# qdr2_3.net
KiCad netlist of a schematic drawn in Altium Designer
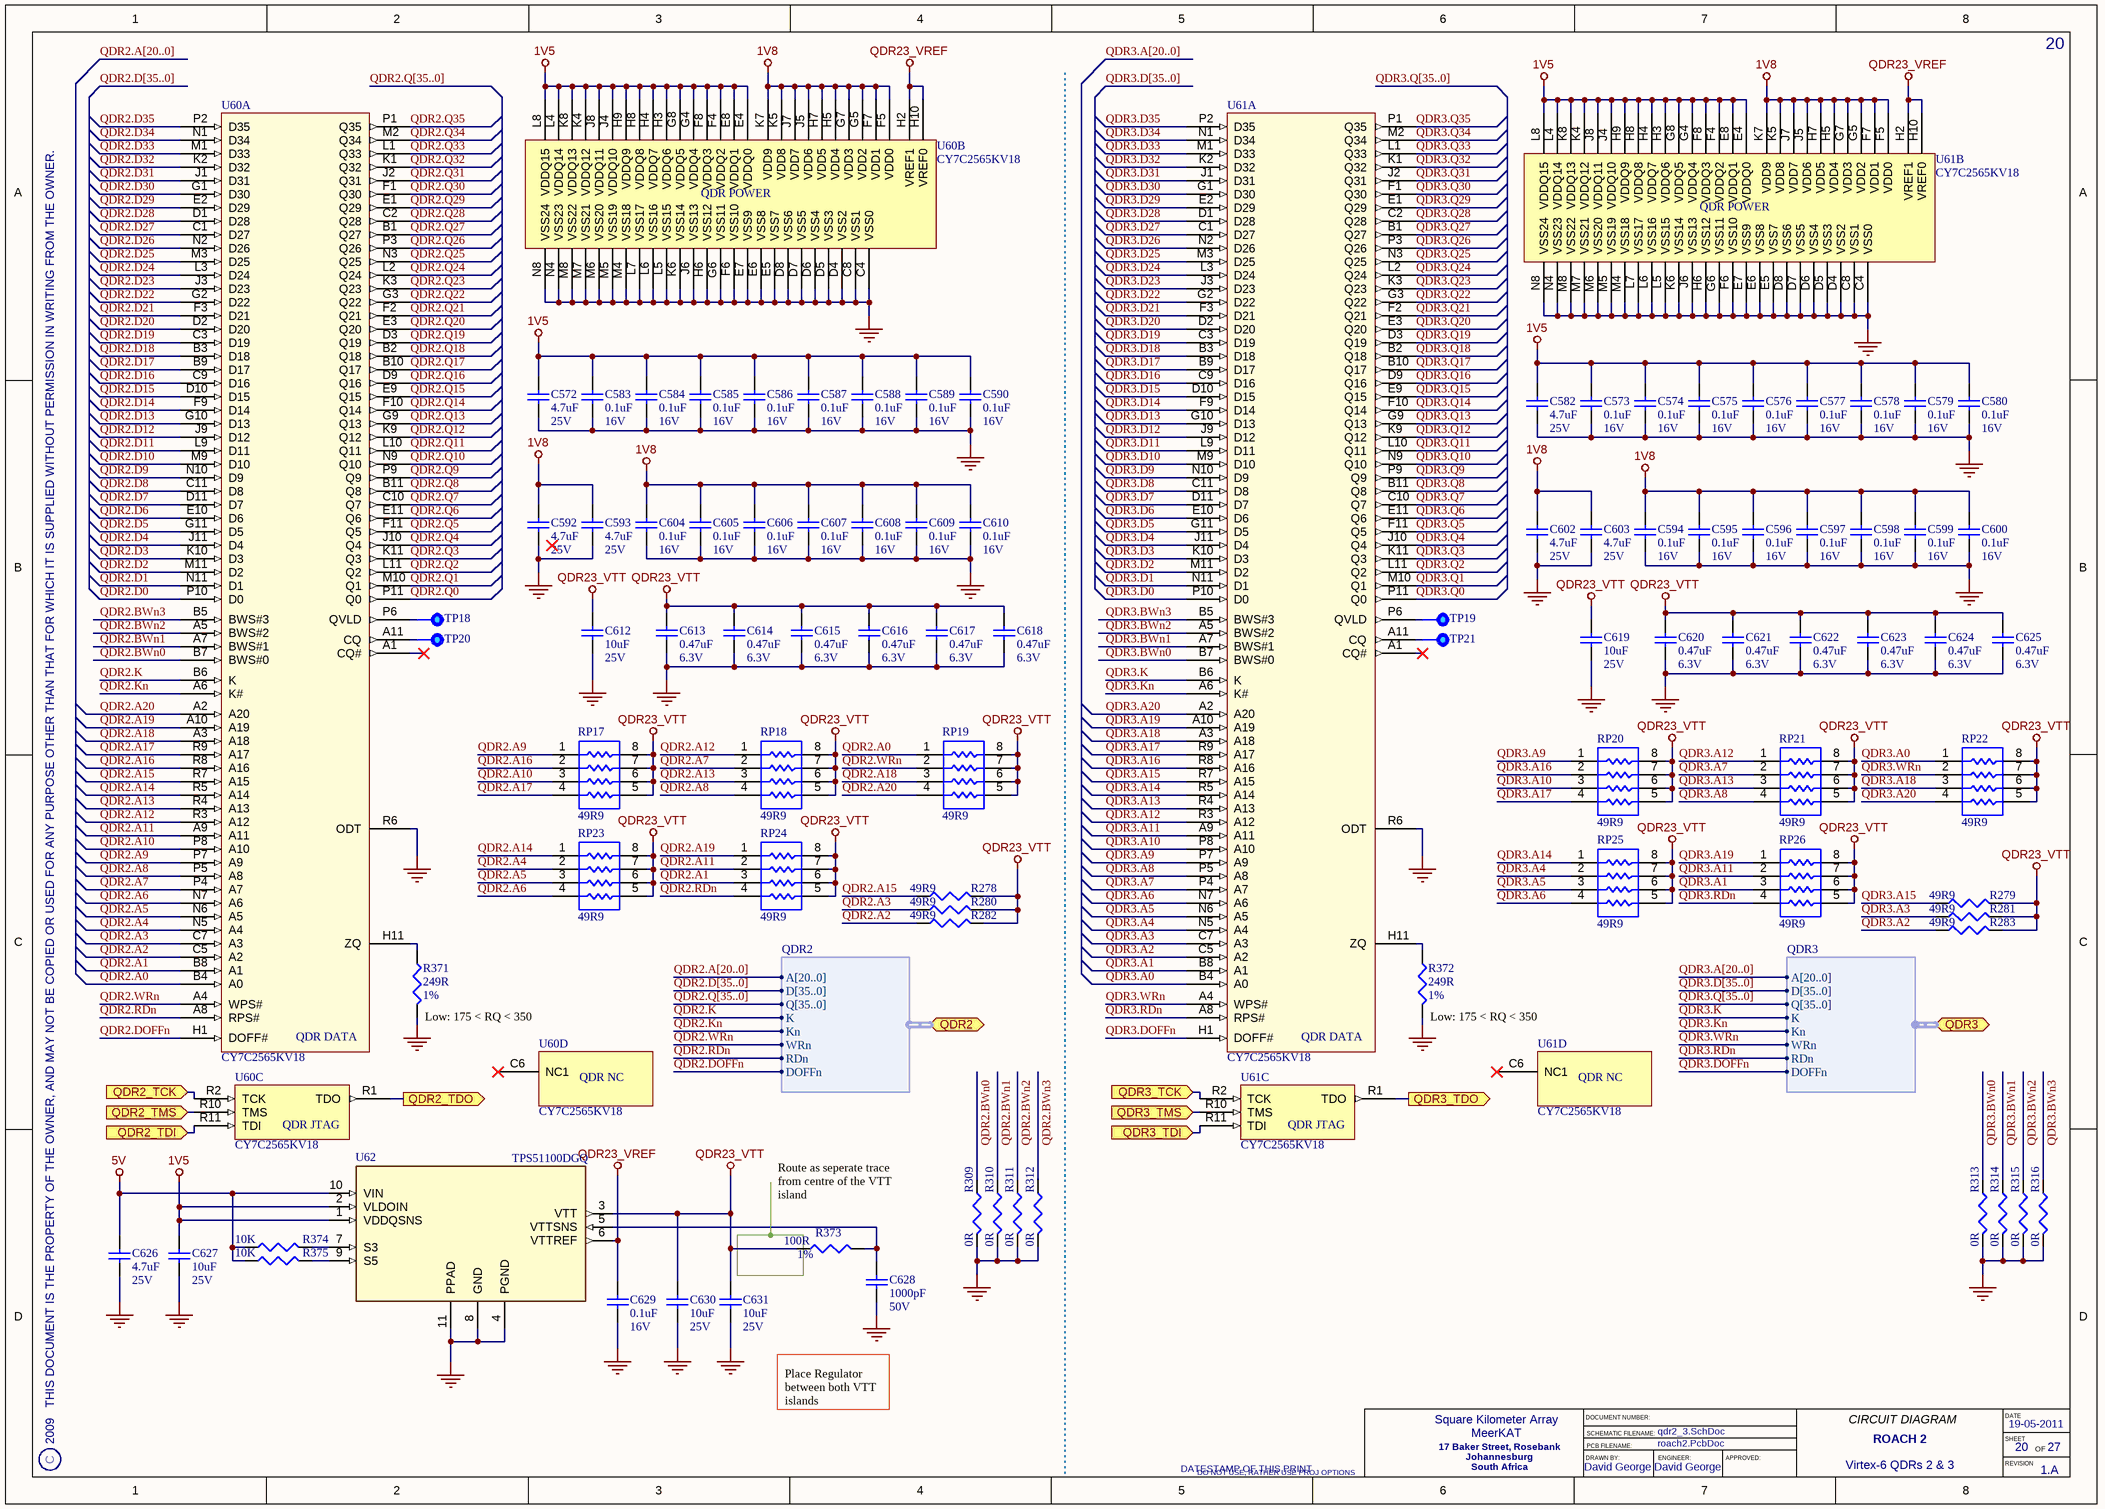
[diagram p0: qdr2_3.SchDoc]

(export (version "E")
  (design (tool "Eeschema 10.0.6"))
  (components
    (comp (ref "C572")
      (value "4.7uF")
      (footprint "CAPC2012X127L")
      (description "4.7uF, Ceramic Capacitor")
      (fields
        (field (name "RATING") "25V")
        (field (name "MANUFACTURER") "MURATA")
        (field (name "PARTNUM") "GRM21BR61E475KA12K")
      )
      (libsource (lib "altium_db") (part "CapStd"))
    )
    (comp (ref "C573")
      (value "0.1uF")
      (footprint "CAPC1005X60L")
      (description "0.1uF, Ceramic Capacitor")
      (fields
        (field (name "RATING") "16V")
        (field (name "MANUFACTURER") "VENKEL")
        (field (name "PARTNUM") "C0402X7R160-104KN")
      )
      (libsource (lib "altium_db") (part "CapStd"))
    )
    (comp (ref "C574")
      (value "0.1uF")
      (footprint "CAPC1005X60L")
      (description "0.1uF, Ceramic Capacitor")
      (fields
        (field (name "RATING") "16V")
        (field (name "MANUFACTURER") "VENKEL")
        (field (name "PARTNUM") "C0402X7R160-104KN")
      )
      (libsource (lib "altium_db") (part "CapStd"))
    )
    (comp (ref "C575")
      (value "0.1uF")
      (footprint "CAPC1005X60L")
      (description "0.1uF, Ceramic Capacitor")
      (fields
        (field (name "RATING") "16V")
        (field (name "MANUFACTURER") "VENKEL")
        (field (name "PARTNUM") "C0402X7R160-104KN")
      )
      (libsource (lib "altium_db") (part "CapStd"))
    )
    (comp (ref "C576")
      (value "0.1uF")
      (footprint "CAPC1005X60L")
      (description "0.1uF, Ceramic Capacitor")
      (fields
        (field (name "RATING") "16V")
        (field (name "MANUFACTURER") "VENKEL")
        (field (name "PARTNUM") "C0402X7R160-104KN")
      )
      (libsource (lib "altium_db") (part "CapStd"))
    )
    (comp (ref "C577")
      (value "0.1uF")
      (footprint "CAPC1005X60L")
      (description "0.1uF, Ceramic Capacitor")
      (fields
        (field (name "RATING") "16V")
        (field (name "MANUFACTURER") "VENKEL")
        (field (name "PARTNUM") "C0402X7R160-104KN")
      )
      (libsource (lib "altium_db") (part "CapStd"))
    )
    (comp (ref "C578")
      (value "0.1uF")
      (footprint "CAPC1005X60L")
      (description "0.1uF, Ceramic Capacitor")
      (fields
        (field (name "RATING") "16V")
        (field (name "MANUFACTURER") "VENKEL")
        (field (name "PARTNUM") "C0402X7R160-104KN")
      )
      (libsource (lib "altium_db") (part "CapStd"))
    )
    (comp (ref "C579")
      (value "0.1uF")
      (footprint "CAPC1005X60L")
      (description "0.1uF, Ceramic Capacitor")
      (fields
        (field (name "RATING") "16V")
        (field (name "MANUFACTURER") "VENKEL")
        (field (name "PARTNUM") "C0402X7R160-104KN")
      )
      (libsource (lib "altium_db") (part "CapStd"))
    )
    (comp (ref "C580")
      (value "0.1uF")
      (footprint "CAPC1005X60L")
      (description "0.1uF, Ceramic Capacitor")
      (fields
        (field (name "RATING") "16V")
        (field (name "MANUFACTURER") "VENKEL")
        (field (name "PARTNUM") "C0402X7R160-104KN")
      )
      (libsource (lib "altium_db") (part "CapStd"))
    )
    (comp (ref "C582")
      (value "4.7uF")
      (footprint "CAPC2012X127L")
      (description "4.7uF, Ceramic Capacitor")
      (fields
        (field (name "RATING") "25V")
        (field (name "MANUFACTURER") "MURATA")
        (field (name "PARTNUM") "GRM21BR61E475KA12K")
      )
      (libsource (lib "altium_db") (part "CapStd"))
    )
    (comp (ref "C583")
      (value "0.1uF")
      (footprint "CAPC1005X60L")
      (description "0.1uF, Ceramic Capacitor")
      (fields
        (field (name "RATING") "16V")
        (field (name "MANUFACTURER") "VENKEL")
        (field (name "PARTNUM") "C0402X7R160-104KN")
      )
      (libsource (lib "altium_db") (part "CapStd"))
    )
    (comp (ref "C584")
      (value "0.1uF")
      (footprint "CAPC1005X60L")
      (description "0.1uF, Ceramic Capacitor")
      (fields
        (field (name "RATING") "16V")
        (field (name "MANUFACTURER") "VENKEL")
        (field (name "PARTNUM") "C0402X7R160-104KN")
      )
      (libsource (lib "altium_db") (part "CapStd"))
    )
    (comp (ref "C585")
      (value "0.1uF")
      (footprint "CAPC1005X60L")
      (description "0.1uF, Ceramic Capacitor")
      (fields
        (field (name "RATING") "16V")
        (field (name "MANUFACTURER") "VENKEL")
        (field (name "PARTNUM") "C0402X7R160-104KN")
      )
      (libsource (lib "altium_db") (part "CapStd"))
    )
    (comp (ref "C586")
      (value "0.1uF")
      (footprint "CAPC1005X60L")
      (description "0.1uF, Ceramic Capacitor")
      (fields
        (field (name "RATING") "16V")
        (field (name "MANUFACTURER") "VENKEL")
        (field (name "PARTNUM") "C0402X7R160-104KN")
      )
      (libsource (lib "altium_db") (part "CapStd"))
    )
    (comp (ref "C587")
      (value "0.1uF")
      (footprint "CAPC1005X60L")
      (description "0.1uF, Ceramic Capacitor")
      (fields
        (field (name "RATING") "16V")
        (field (name "MANUFACTURER") "VENKEL")
        (field (name "PARTNUM") "C0402X7R160-104KN")
      )
      (libsource (lib "altium_db") (part "CapStd"))
    )
    (comp (ref "C588")
      (value "0.1uF")
      (footprint "CAPC1005X60L")
      (description "0.1uF, Ceramic Capacitor")
      (fields
        (field (name "RATING") "16V")
        (field (name "MANUFACTURER") "VENKEL")
        (field (name "PARTNUM") "C0402X7R160-104KN")
      )
      (libsource (lib "altium_db") (part "CapStd"))
    )
    (comp (ref "C589")
      (value "0.1uF")
      (footprint "CAPC1005X60L")
      (description "0.1uF, Ceramic Capacitor")
      (fields
        (field (name "RATING") "16V")
        (field (name "MANUFACTURER") "VENKEL")
        (field (name "PARTNUM") "C0402X7R160-104KN")
      )
      (libsource (lib "altium_db") (part "CapStd"))
    )
    (comp (ref "C590")
      (value "0.1uF")
      (footprint "CAPC1005X60L")
      (description "0.1uF, Ceramic Capacitor")
      (fields
        (field (name "RATING") "16V")
        (field (name "MANUFACTURER") "VENKEL")
        (field (name "PARTNUM") "C0402X7R160-104KN")
      )
      (libsource (lib "altium_db") (part "CapStd"))
    )
    (comp (ref "C592")
      (value "4.7uF")
      (footprint "CAPC2012X127L")
      (description "4.7uF, Ceramic Capacitor")
      (fields
        (field (name "RATING") "25V")
        (field (name "MANUFACTURER") "MURATA")
        (field (name "PARTNUM") "GRM21BR61E475KA12K")
      )
      (libsource (lib "altium_db") (part "CapStd"))
    )
    (comp (ref "C593")
      (value "4.7uF")
      (footprint "CAPC2012X127L")
      (description "4.7uF, Ceramic Capacitor")
      (fields
        (field (name "RATING") "25V")
        (field (name "MANUFACTURER") "MURATA")
        (field (name "PARTNUM") "GRM21BR61E475KA12K")
      )
      (libsource (lib "altium_db") (part "CapStd"))
    )
    (comp (ref "C594")
      (value "0.1uF")
      (footprint "CAPC1005X60L")
      (description "0.1uF, Ceramic Capacitor")
      (fields
        (field (name "RATING") "16V")
        (field (name "MANUFACTURER") "VENKEL")
        (field (name "PARTNUM") "C0402X7R160-104KN")
      )
      (libsource (lib "altium_db") (part "CapStd"))
    )
    (comp (ref "C595")
      (value "0.1uF")
      (footprint "CAPC1005X60L")
      (description "0.1uF, Ceramic Capacitor")
      (fields
        (field (name "RATING") "16V")
        (field (name "MANUFACTURER") "VENKEL")
        (field (name "PARTNUM") "C0402X7R160-104KN")
      )
      (libsource (lib "altium_db") (part "CapStd"))
    )
    (comp (ref "C596")
      (value "0.1uF")
      (footprint "CAPC1005X60L")
      (description "0.1uF, Ceramic Capacitor")
      (fields
        (field (name "RATING") "16V")
        (field (name "MANUFACTURER") "VENKEL")
        (field (name "PARTNUM") "C0402X7R160-104KN")
      )
      (libsource (lib "altium_db") (part "CapStd"))
    )
    (comp (ref "C597")
      (value "0.1uF")
      (footprint "CAPC1005X60L")
      (description "0.1uF, Ceramic Capacitor")
      (fields
        (field (name "RATING") "16V")
        (field (name "MANUFACTURER") "VENKEL")
        (field (name "PARTNUM") "C0402X7R160-104KN")
      )
      (libsource (lib "altium_db") (part "CapStd"))
    )
    (comp (ref "C598")
      (value "0.1uF")
      (footprint "CAPC1005X60L")
      (description "0.1uF, Ceramic Capacitor")
      (fields
        (field (name "RATING") "16V")
        (field (name "MANUFACTURER") "VENKEL")
        (field (name "PARTNUM") "C0402X7R160-104KN")
      )
      (libsource (lib "altium_db") (part "CapStd"))
    )
    (comp (ref "C599")
      (value "0.1uF")
      (footprint "CAPC1005X60L")
      (description "0.1uF, Ceramic Capacitor")
      (fields
        (field (name "RATING") "16V")
        (field (name "MANUFACTURER") "VENKEL")
        (field (name "PARTNUM") "C0402X7R160-104KN")
      )
      (libsource (lib "altium_db") (part "CapStd"))
    )
    (comp (ref "C600")
      (value "0.1uF")
      (footprint "CAPC1005X60L")
      (description "0.1uF, Ceramic Capacitor")
      (fields
        (field (name "RATING") "16V")
        (field (name "MANUFACTURER") "VENKEL")
        (field (name "PARTNUM") "C0402X7R160-104KN")
      )
      (libsource (lib "altium_db") (part "CapStd"))
    )
    (comp (ref "C602")
      (value "4.7uF")
      (footprint "CAPC2012X127L")
      (description "4.7uF, Ceramic Capacitor")
      (fields
        (field (name "RATING") "25V")
        (field (name "MANUFACTURER") "MURATA")
        (field (name "PARTNUM") "GRM21BR61E475KA12K")
      )
      (libsource (lib "altium_db") (part "CapStd"))
    )
    (comp (ref "C603")
      (value "4.7uF")
      (footprint "CAPC2012X127L")
      (description "4.7uF, Ceramic Capacitor")
      (fields
        (field (name "RATING") "25V")
        (field (name "MANUFACTURER") "MURATA")
        (field (name "PARTNUM") "GRM21BR61E475KA12K")
      )
      (libsource (lib "altium_db") (part "CapStd"))
    )
    (comp (ref "C604")
      (value "0.1uF")
      (footprint "CAPC1005X60L")
      (description "0.1uF, Ceramic Capacitor")
      (fields
        (field (name "RATING") "16V")
        (field (name "MANUFACTURER") "VENKEL")
        (field (name "PARTNUM") "C0402X7R160-104KN")
      )
      (libsource (lib "altium_db") (part "CapStd"))
    )
    (comp (ref "C605")
      (value "0.1uF")
      (footprint "CAPC1005X60L")
      (description "0.1uF, Ceramic Capacitor")
      (fields
        (field (name "RATING") "16V")
        (field (name "MANUFACTURER") "VENKEL")
        (field (name "PARTNUM") "C0402X7R160-104KN")
      )
      (libsource (lib "altium_db") (part "CapStd"))
    )
    (comp (ref "C606")
      (value "0.1uF")
      (footprint "CAPC1005X60L")
      (description "0.1uF, Ceramic Capacitor")
      (fields
        (field (name "RATING") "16V")
        (field (name "MANUFACTURER") "VENKEL")
        (field (name "PARTNUM") "C0402X7R160-104KN")
      )
      (libsource (lib "altium_db") (part "CapStd"))
    )
    (comp (ref "C607")
      (value "0.1uF")
      (footprint "CAPC1005X60L")
      (description "0.1uF, Ceramic Capacitor")
      (fields
        (field (name "RATING") "16V")
        (field (name "MANUFACTURER") "VENKEL")
        (field (name "PARTNUM") "C0402X7R160-104KN")
      )
      (libsource (lib "altium_db") (part "CapStd"))
    )
    (comp (ref "C608")
      (value "0.1uF")
      (footprint "CAPC1005X60L")
      (description "0.1uF, Ceramic Capacitor")
      (fields
        (field (name "RATING") "16V")
        (field (name "MANUFACTURER") "VENKEL")
        (field (name "PARTNUM") "C0402X7R160-104KN")
      )
      (libsource (lib "altium_db") (part "CapStd"))
    )
    (comp (ref "C609")
      (value "0.1uF")
      (footprint "CAPC1005X60L")
      (description "0.1uF, Ceramic Capacitor")
      (fields
        (field (name "RATING") "16V")
        (field (name "MANUFACTURER") "VENKEL")
        (field (name "PARTNUM") "C0402X7R160-104KN")
      )
      (libsource (lib "altium_db") (part "CapStd"))
    )
    (comp (ref "C610")
      (value "0.1uF")
      (footprint "CAPC1005X60L")
      (description "0.1uF, Ceramic Capacitor")
      (fields
        (field (name "RATING") "16V")
        (field (name "MANUFACTURER") "VENKEL")
        (field (name "PARTNUM") "C0402X7R160-104KN")
      )
      (libsource (lib "altium_db") (part "CapStd"))
    )
    (comp (ref "C612")
      (value "10uF")
      (footprint "CAPC3225X200L")
      (description "10uF, Ceramic Capacitor")
      (fields
        (field (name "RATING") "25V")
        (field (name "MANUFACTURER") "MURATA")
        (field (name "PARTNUM") "GRM32DR61E106KA12L")
      )
      (libsource (lib "altium_db") (part "CapStd"))
    )
    (comp (ref "C613")
      (value "0.47uF")
      (footprint "CAPC1005X55L")
      (description "0.47uF, Ceramic Capacitor")
      (fields
        (field (name "RATING") "6.3V")
        (field (name "MANUFACTURER") "MURATA")
        (field (name "PARTNUM") "GRM155R60J474KE19")
      )
      (libsource (lib "altium_db") (part "CapStd"))
    )
    (comp (ref "C614")
      (value "0.47uF")
      (footprint "CAPC1005X55L")
      (description "0.47uF, Ceramic Capacitor")
      (fields
        (field (name "RATING") "6.3V")
        (field (name "MANUFACTURER") "MURATA")
        (field (name "PARTNUM") "GRM155R60J474KE19")
      )
      (libsource (lib "altium_db") (part "CapStd"))
    )
    (comp (ref "C615")
      (value "0.47uF")
      (footprint "CAPC1005X55L")
      (description "0.47uF, Ceramic Capacitor")
      (fields
        (field (name "RATING") "6.3V")
        (field (name "MANUFACTURER") "MURATA")
        (field (name "PARTNUM") "GRM155R60J474KE19")
      )
      (libsource (lib "altium_db") (part "CapStd"))
    )
    (comp (ref "C616")
      (value "0.47uF")
      (footprint "CAPC1005X55L")
      (description "0.47uF, Ceramic Capacitor")
      (fields
        (field (name "RATING") "6.3V")
        (field (name "MANUFACTURER") "MURATA")
        (field (name "PARTNUM") "GRM155R60J474KE19")
      )
      (libsource (lib "altium_db") (part "CapStd"))
    )
    (comp (ref "C617")
      (value "0.47uF")
      (footprint "CAPC1005X55L")
      (description "0.47uF, Ceramic Capacitor")
      (fields
        (field (name "RATING") "6.3V")
        (field (name "MANUFACTURER") "MURATA")
        (field (name "PARTNUM") "GRM155R60J474KE19")
      )
      (libsource (lib "altium_db") (part "CapStd"))
    )
    (comp (ref "C618")
      (value "0.47uF")
      (footprint "CAPC1005X55L")
      (description "0.47uF, Ceramic Capacitor")
      (fields
        (field (name "RATING") "6.3V")
        (field (name "MANUFACTURER") "MURATA")
        (field (name "PARTNUM") "GRM155R60J474KE19")
      )
      (libsource (lib "altium_db") (part "CapStd"))
    )
    (comp (ref "C619")
      (value "10uF")
      (footprint "CAPC3225X200L")
      (description "10uF, Ceramic Capacitor")
      (fields
        (field (name "RATING") "25V")
        (field (name "MANUFACTURER") "MURATA")
        (field (name "PARTNUM") "GRM32DR61E106KA12L")
      )
      (libsource (lib "altium_db") (part "CapStd"))
    )
    (comp (ref "C620")
      (value "0.47uF")
      (footprint "CAPC1005X55L")
      (description "0.47uF, Ceramic Capacitor")
      (fields
        (field (name "RATING") "6.3V")
        (field (name "MANUFACTURER") "MURATA")
        (field (name "PARTNUM") "GRM155R60J474KE19")
      )
      (libsource (lib "altium_db") (part "CapStd"))
    )
    (comp (ref "C621")
      (value "0.47uF")
      (footprint "CAPC1005X55L")
      (description "0.47uF, Ceramic Capacitor")
      (fields
        (field (name "RATING") "6.3V")
        (field (name "MANUFACTURER") "MURATA")
        (field (name "PARTNUM") "GRM155R60J474KE19")
      )
      (libsource (lib "altium_db") (part "CapStd"))
    )
    (comp (ref "C622")
      (value "0.47uF")
      (footprint "CAPC1005X55L")
      (description "0.47uF, Ceramic Capacitor")
      (fields
        (field (name "RATING") "6.3V")
        (field (name "MANUFACTURER") "MURATA")
        (field (name "PARTNUM") "GRM155R60J474KE19")
      )
      (libsource (lib "altium_db") (part "CapStd"))
    )
    (comp (ref "C623")
      (value "0.47uF")
      (footprint "CAPC1005X55L")
      (description "0.47uF, Ceramic Capacitor")
      (fields
        (field (name "RATING") "6.3V")
        (field (name "MANUFACTURER") "MURATA")
        (field (name "PARTNUM") "GRM155R60J474KE19")
      )
      (libsource (lib "altium_db") (part "CapStd"))
    )
    (comp (ref "C624")
      (value "0.47uF")
      (footprint "CAPC1005X55L")
      (description "0.47uF, Ceramic Capacitor")
      (fields
        (field (name "RATING") "6.3V")
        (field (name "MANUFACTURER") "MURATA")
        (field (name "PARTNUM") "GRM155R60J474KE19")
      )
      (libsource (lib "altium_db") (part "CapStd"))
    )
    (comp (ref "C625")
      (value "0.47uF")
      (footprint "CAPC1005X55L")
      (description "0.47uF, Ceramic Capacitor")
      (fields
        (field (name "RATING") "6.3V")
        (field (name "MANUFACTURER") "MURATA")
        (field (name "PARTNUM") "GRM155R60J474KE19")
      )
      (libsource (lib "altium_db") (part "CapStd"))
    )
    (comp (ref "C626")
      (value "4.7uF")
      (footprint "CAPC2012X127L")
      (description "4.7uF, Ceramic Capacitor")
      (fields
        (field (name "RATING") "25V")
        (field (name "MANUFACTURER") "MURATA")
        (field (name "PARTNUM") "GRM21BR61E475KA12K")
      )
      (libsource (lib "altium_db") (part "CapStd"))
    )
    (comp (ref "C627")
      (value "10uF")
      (footprint "CAPC3225X200L")
      (description "10uF, Ceramic Capacitor")
      (fields
        (field (name "RATING") "25V")
        (field (name "MANUFACTURER") "MURATA")
        (field (name "PARTNUM") "GRM32DR61E106KA12L")
      )
      (libsource (lib "altium_db") (part "CapStd"))
    )
    (comp (ref "C628")
      (value "1000pF")
      (footprint "CAPC1005X55L")
      (description "1000pF, Ceramic Capacitor")
      (fields
        (field (name "RATING") "50V")
        (field (name "MANUFACTURER") "MURATA")
        (field (name "PARTNUM") "GRM155R61H102KA01D")
      )
      (libsource (lib "altium_db") (part "CapStd"))
    )
    (comp (ref "C629")
      (value "0.1uF")
      (footprint "CAPC1005X60L")
      (description "0.1uF, Ceramic Capacitor")
      (fields
        (field (name "RATING") "16V")
        (field (name "MANUFACTURER") "VENKEL")
        (field (name "PARTNUM") "C0402X7R160-104KN")
      )
      (libsource (lib "altium_db") (part "CapStd"))
    )
    (comp (ref "C630")
      (value "10uF")
      (footprint "CAPC3225X200L")
      (description "10uF, Ceramic Capacitor")
      (fields
        (field (name "RATING") "25V")
        (field (name "MANUFACTURER") "MURATA")
        (field (name "PARTNUM") "GRM32DR61E106KA12L")
      )
      (libsource (lib "altium_db") (part "CapStd"))
    )
    (comp (ref "C631")
      (value "10uF")
      (footprint "CAPC3225X200L")
      (description "10uF, Ceramic Capacitor")
      (fields
        (field (name "RATING") "25V")
        (field (name "MANUFACTURER") "MURATA")
        (field (name "PARTNUM") "GRM32DR61E106KA12L")
      )
      (libsource (lib "altium_db") (part "CapStd"))
    )
    (comp (ref "R278")
      (value "49R9")
      (footprint "RESC1005X40L")
      (description "49R9, 1.1mm x 0.5mm, Thick Film Resistor")
      (fields (field (name "MANUFACTURER") "ROYALOHM") (field (name "PARTNUM") "0402WGF499JT1E"))
      (libsource (lib "altium_db") (part "ResStd"))
    )
    (comp (ref "R279")
      (value "49R9")
      (footprint "RESC1005X40L")
      (description "49R9, 1.1mm x 0.5mm, Thick Film Resistor")
      (fields (field (name "MANUFACTURER") "ROYALOHM") (field (name "PARTNUM") "0402WGF499JT1E"))
      (libsource (lib "altium_db") (part "ResStd"))
    )
    (comp (ref "R280")
      (value "49R9")
      (footprint "RESC1005X40L")
      (description "49R9, 1.1mm x 0.5mm, Thick Film Resistor")
      (fields (field (name "MANUFACTURER") "ROYALOHM") (field (name "PARTNUM") "0402WGF499JT1E"))
      (libsource (lib "altium_db") (part "ResStd"))
    )
    (comp (ref "R281")
      (value "49R9")
      (footprint "RESC1005X40L")
      (description "49R9, 1.1mm x 0.5mm, Thick Film Resistor")
      (fields (field (name "MANUFACTURER") "ROYALOHM") (field (name "PARTNUM") "0402WGF499JT1E"))
      (libsource (lib "altium_db") (part "ResStd"))
    )
    (comp (ref "R282")
      (value "49R9")
      (footprint "RESC1005X40L")
      (description "49R9, 1.1mm x 0.5mm, Thick Film Resistor")
      (fields (field (name "MANUFACTURER") "ROYALOHM") (field (name "PARTNUM") "0402WGF499JT1E"))
      (libsource (lib "altium_db") (part "ResStd"))
    )
    (comp (ref "R283")
      (value "49R9")
      (footprint "RESC1005X40L")
      (description "49R9, 1.1mm x 0.5mm, Thick Film Resistor")
      (fields (field (name "MANUFACTURER") "ROYALOHM") (field (name "PARTNUM") "0402WGF499JT1E"))
      (libsource (lib "altium_db") (part "ResStd"))
    )
    (comp (ref "R309")
      (value "0R")
      (footprint "RESC1005X40L")
      (description "0R, 1.1mm x 0.5mm, Thick Film Resistor")
      (fields (field (name "MANUFACTURER") "ROYALOHM") (field (name "PARTNUM") "0402WG00000T1E"))
      (libsource (lib "altium_db") (part "ResStd"))
    )
    (comp (ref "R310")
      (value "0R")
      (footprint "RESC1005X40L")
      (description "0R, 1.1mm x 0.5mm, Thick Film Resistor")
      (fields (field (name "MANUFACTURER") "ROYALOHM") (field (name "PARTNUM") "0402WG00000T1E"))
      (libsource (lib "altium_db") (part "ResStd"))
    )
    (comp (ref "R311")
      (value "0R")
      (footprint "RESC1005X40L")
      (description "0R, 1.1mm x 0.5mm, Thick Film Resistor")
      (fields (field (name "MANUFACTURER") "ROYALOHM") (field (name "PARTNUM") "0402WG00000T1E"))
      (libsource (lib "altium_db") (part "ResStd"))
    )
    (comp (ref "R312")
      (value "0R")
      (footprint "RESC1005X40L")
      (description "0R, 1.1mm x 0.5mm, Thick Film Resistor")
      (fields (field (name "MANUFACTURER") "ROYALOHM") (field (name "PARTNUM") "0402WG00000T1E"))
      (libsource (lib "altium_db") (part "ResStd"))
    )
    (comp (ref "R313")
      (value "0R")
      (footprint "RESC1005X40L")
      (description "0R, 1.1mm x 0.5mm, Thick Film Resistor")
      (fields (field (name "MANUFACTURER") "ROYALOHM") (field (name "PARTNUM") "0402WG00000T1E"))
      (libsource (lib "altium_db") (part "ResStd"))
    )
    (comp (ref "R314")
      (value "0R")
      (footprint "RESC1005X40L")
      (description "0R, 1.1mm x 0.5mm, Thick Film Resistor")
      (fields (field (name "MANUFACTURER") "ROYALOHM") (field (name "PARTNUM") "0402WG00000T1E"))
      (libsource (lib "altium_db") (part "ResStd"))
    )
    (comp (ref "R315")
      (value "0R")
      (footprint "RESC1005X40L")
      (description "0R, 1.1mm x 0.5mm, Thick Film Resistor")
      (fields (field (name "MANUFACTURER") "ROYALOHM") (field (name "PARTNUM") "0402WG00000T1E"))
      (libsource (lib "altium_db") (part "ResStd"))
    )
    (comp (ref "R316")
      (value "0R")
      (footprint "RESC1005X40L")
      (description "0R, 1.1mm x 0.5mm, Thick Film Resistor")
      (fields (field (name "MANUFACTURER") "ROYALOHM") (field (name "PARTNUM") "0402WG00000T1E"))
      (libsource (lib "altium_db") (part "ResStd"))
    )
    (comp (ref "R371")
      (value "249R")
      (footprint "RESC1005X40L")
      (description "249R, 1.1mm x 0.5mm, Thick Film Resistor")
      (fields
        (field (name "MANUFACTURER") "ROYALOHM")
        (field (name "PARTNUM") "0402WGF2490T1E")
        (field (name "TOLERANCE") "1%")
      )
      (libsource (lib "altium_db") (part "ResStd"))
    )
    (comp (ref "R372")
      (value "249R")
      (footprint "RESC1005X40L")
      (description "249R, 1.1mm x 0.5mm, Thick Film Resistor")
      (fields
        (field (name "MANUFACTURER") "ROYALOHM")
        (field (name "PARTNUM") "0402WGF2490T1E")
        (field (name "TOLERANCE") "1%")
      )
      (libsource (lib "altium_db") (part "ResStd"))
    )
    (comp (ref "R373")
      (value "100R")
      (footprint "RESC1005X40L")
      (description "100R, 1.1mm x 0.5mm, Thick Film Resistor")
      (fields
        (field (name "MANUFACTURER") "ROYALOHM")
        (field (name "PARTNUM") "0402WGF0101T1E")
        (field (name "TOLERANCE") "1%")
      )
      (libsource (lib "altium_db") (part "ResStd"))
    )
    (comp (ref "R374")
      (value "10K")
      (footprint "RESC1005X40L")
      (description "10K, 1.1mm x 0.5mm, Thick Film Resistor")
      (fields (field (name "MANUFACTURER") "ROYALOHM") (field (name "PARTNUM") "0402WGJ0103T1E"))
      (libsource (lib "altium_db") (part "ResStd"))
    )
    (comp (ref "R375")
      (value "10K")
      (footprint "RESC1005X40L")
      (description "10K, 1.1mm x 0.5mm, Thick Film Resistor")
      (fields (field (name "MANUFACTURER") "ROYALOHM") (field (name "PARTNUM") "0402WGJ0103T1E"))
      (libsource (lib "altium_db") (part "ResStd"))
    )
    (comp (ref "RP17")
      (value "49R9")
      (footprint "RESCAV50P100X200X45-8L")
      (description "4-Wide, Isolated, Thick Film Resistor Network")
      (fields (field (name "MANUFACTURER") "ROYALOHM") (field (name "PARTNUM") "4D02WGJ0510B1E"))
      (libsource (lib "altium_db") (part "ResPack4"))
    )
    (comp (ref "RP18")
      (value "49R9")
      (footprint "RESCAV50P100X200X45-8L")
      (description "4-Wide, Isolated, Thick Film Resistor Network")
      (fields (field (name "MANUFACTURER") "ROYALOHM") (field (name "PARTNUM") "4D02WGJ0510B1E"))
      (libsource (lib "altium_db") (part "ResPack4"))
    )
    (comp (ref "RP19")
      (value "49R9")
      (footprint "RESCAV50P100X200X45-8L")
      (description "4-Wide, Isolated, Thick Film Resistor Network")
      (fields (field (name "MANUFACTURER") "ROYALOHM") (field (name "PARTNUM") "4D02WGJ0510B1E"))
      (libsource (lib "altium_db") (part "ResPack4"))
    )
    (comp (ref "RP20")
      (value "49R9")
      (footprint "RESCAV50P100X200X45-8L")
      (description "4-Wide, Isolated, Thick Film Resistor Network")
      (fields (field (name "MANUFACTURER") "ROYALOHM") (field (name "PARTNUM") "4D02WGJ0510B1E"))
      (libsource (lib "altium_db") (part "ResPack4"))
    )
    (comp (ref "RP21")
      (value "49R9")
      (footprint "RESCAV50P100X200X45-8L")
      (description "4-Wide, Isolated, Thick Film Resistor Network")
      (fields (field (name "MANUFACTURER") "ROYALOHM") (field (name "PARTNUM") "4D02WGJ0510B1E"))
      (libsource (lib "altium_db") (part "ResPack4"))
    )
    (comp (ref "RP22")
      (value "49R9")
      (footprint "RESCAV50P100X200X45-8L")
      (description "4-Wide, Isolated, Thick Film Resistor Network")
      (fields (field (name "MANUFACTURER") "ROYALOHM") (field (name "PARTNUM") "4D02WGJ0510B1E"))
      (libsource (lib "altium_db") (part "ResPack4"))
    )
    (comp (ref "RP23")
      (value "49R9")
      (footprint "RESCAV50P100X200X45-8L")
      (description "4-Wide, Isolated, Thick Film Resistor Network")
      (fields (field (name "MANUFACTURER") "ROYALOHM") (field (name "PARTNUM") "4D02WGJ0510B1E"))
      (libsource (lib "altium_db") (part "ResPack4"))
    )
    (comp (ref "RP24")
      (value "49R9")
      (footprint "RESCAV50P100X200X45-8L")
      (description "4-Wide, Isolated, Thick Film Resistor Network")
      (fields (field (name "MANUFACTURER") "ROYALOHM") (field (name "PARTNUM") "4D02WGJ0510B1E"))
      (libsource (lib "altium_db") (part "ResPack4"))
    )
    (comp (ref "RP25")
      (value "49R9")
      (footprint "RESCAV50P100X200X45-8L")
      (description "4-Wide, Isolated, Thick Film Resistor Network")
      (fields (field (name "MANUFACTURER") "ROYALOHM") (field (name "PARTNUM") "4D02WGJ0510B1E"))
      (libsource (lib "altium_db") (part "ResPack4"))
    )
    (comp (ref "RP26")
      (value "49R9")
      (footprint "RESCAV50P100X200X45-8L")
      (description "4-Wide, Isolated, Thick Film Resistor Network")
      (fields (field (name "MANUFACTURER") "ROYALOHM") (field (name "PARTNUM") "4D02WGJ0510B1E"))
      (libsource (lib "altium_db") (part "ResPack4"))
    )
    (comp (ref "TP18")
      (value "Testpoint")
      (footprint "TP100")
      (description "1mm Diameter, through-hole, Circular Test-point")
      (libsource (lib "altium_db") (part "Testpoint"))
    )
    (comp (ref "TP19")
      (value "Testpoint")
      (footprint "TP100")
      (description "1mm Diameter, through-hole, Circular Test-point")
      (libsource (lib "altium_db") (part "Testpoint"))
    )
    (comp (ref "TP20")
      (value "Testpoint")
      (footprint "TP100")
      (description "1mm Diameter, through-hole, Circular Test-point")
      (libsource (lib "altium_db") (part "Testpoint"))
    )
    (comp (ref "TP21")
      (value "Testpoint")
      (footprint "TP100")
      (description "1mm Diameter, through-hole, Circular Test-point")
      (libsource (lib "altium_db") (part "Testpoint"))
    )
    (comp (ref "U60")
      (value "CY7C2565KV18")
      (footprint "FBGA_165-Ball")
      (description "72Mb, 36-Bit wide, QDR2+ Synchronous SRAM with ODT")
      (fields (field (name "MANUFACTURER") "Cypress") (field (name "PARTNUM") "CY7C2565KV18-450BZXC"))
      (libsource (lib "altium_db") (part "QDR2PLUS_36BIT"))
    )
    (comp (ref "U61")
      (value "CY7C2565KV18")
      (footprint "FBGA_165-Ball")
      (description "72Mb, 36-Bit wide, QDR2+ Synchronous SRAM with ODT")
      (fields (field (name "MANUFACTURER") "Cypress") (field (name "PARTNUM") "CY7C2565KV18-450BZXC"))
      (libsource (lib "altium_db") (part "QDR2PLUS_36BIT"))
    )
    (comp (ref "U62")
      (value "TPS51100DGQ")
      (footprint "MSOP_10-N")
      (description "3A Sink/Source Regulator")
      (fields (field (name "MANUFACTURER") "Texas Instruments"))
      (libsource (lib "altium_db") (part "TPS51100DGQ"))
    )
  )
  (nets
    (net (code "3") (name "/QDR2.A0") (class "Default")
      (node (ref "RP19") (pin "1") (pinfunction "1_1") (pintype "passive"))
      (node (ref "U60") (pin "B4") (pinfunction "A0_B4") (pintype "input"))
    )
    (net (code "4") (name "/QDR2.A1") (class "Default")
      (node (ref "RP24") (pin "3") (pinfunction "3_3") (pintype "passive"))
      (node (ref "U60") (pin "B8") (pinfunction "A1_B8") (pintype "input"))
    )
    (net (code "5") (name "/QDR2.A2") (class "Default")
      (node (ref "R282") (pin "1") (pinfunction "1_1") (pintype "passive"))
      (node (ref "U60") (pin "C5") (pinfunction "A2_C5") (pintype "input"))
    )
    (net (code "6") (name "/QDR2.A3") (class "Default")
      (node (ref "R280") (pin "1") (pinfunction "1_1") (pintype "passive"))
      (node (ref "U60") (pin "C7") (pinfunction "A3_C7") (pintype "input"))
    )
    (net (code "7") (name "/QDR2.A4") (class "Default")
      (node (ref "RP23") (pin "2") (pinfunction "2_2") (pintype "passive"))
      (node (ref "U60") (pin "N5") (pinfunction "A4_N5") (pintype "input"))
    )
    (net (code "8") (name "/QDR2.A5") (class "Default")
      (node (ref "RP23") (pin "3") (pinfunction "3_3") (pintype "passive"))
      (node (ref "U60") (pin "N6") (pinfunction "A5_N6") (pintype "input"))
    )
    (net (code "9") (name "/QDR2.A6") (class "Default")
      (node (ref "RP23") (pin "4") (pinfunction "4_4") (pintype "passive"))
      (node (ref "U60") (pin "N7") (pinfunction "A6_N7") (pintype "input"))
    )
    (net (code "10") (name "/QDR2.A7") (class "Default")
      (node (ref "RP18") (pin "2") (pinfunction "2_2") (pintype "passive"))
      (node (ref "U60") (pin "P4") (pinfunction "A7_P4") (pintype "input"))
    )
    (net (code "11") (name "/QDR2.A8") (class "Default")
      (node (ref "RP18") (pin "4") (pinfunction "4_4") (pintype "passive"))
      (node (ref "U60") (pin "P5") (pinfunction "A8_P5") (pintype "input"))
    )
    (net (code "12") (name "/QDR2.A9") (class "Default")
      (node (ref "RP17") (pin "1") (pinfunction "1_1") (pintype "passive"))
      (node (ref "U60") (pin "P7") (pinfunction "A9_P7") (pintype "input"))
    )
    (net (code "13") (name "/QDR2.A10") (class "Default")
      (node (ref "RP17") (pin "3") (pinfunction "3_3") (pintype "passive"))
      (node (ref "U60") (pin "P8") (pinfunction "A10_P8") (pintype "input"))
    )
    (net (code "14") (name "/QDR2.A11") (class "Default")
      (node (ref "RP24") (pin "2") (pinfunction "2_2") (pintype "passive"))
      (node (ref "U60") (pin "A9") (pinfunction "A11_A9") (pintype "input"))
    )
    (net (code "15") (name "/QDR2.A12") (class "Default")
      (node (ref "RP18") (pin "1") (pinfunction "1_1") (pintype "passive"))
      (node (ref "U60") (pin "R3") (pinfunction "A12_R3") (pintype "input"))
    )
    (net (code "16") (name "/QDR2.A13") (class "Default")
      (node (ref "RP18") (pin "3") (pinfunction "3_3") (pintype "passive"))
      (node (ref "U60") (pin "R4") (pinfunction "A13_R4") (pintype "input"))
    )
    (net (code "17") (name "/QDR2.A14") (class "Default")
      (node (ref "RP23") (pin "1") (pinfunction "1_1") (pintype "passive"))
      (node (ref "U60") (pin "R5") (pinfunction "A14_R5") (pintype "input"))
    )
    (net (code "18") (name "/QDR2.A15") (class "Default")
      (node (ref "R278") (pin "1") (pinfunction "1_1") (pintype "passive"))
      (node (ref "U60") (pin "R7") (pinfunction "A15_R7") (pintype "input"))
    )
    (net (code "19") (name "/QDR2.A16") (class "Default")
      (node (ref "RP17") (pin "2") (pinfunction "2_2") (pintype "passive"))
      (node (ref "U60") (pin "R8") (pinfunction "A16_R8") (pintype "input"))
    )
    (net (code "20") (name "/QDR2.A17") (class "Default")
      (node (ref "RP17") (pin "4") (pinfunction "4_4") (pintype "passive"))
      (node (ref "U60") (pin "R9") (pinfunction "A17_R9") (pintype "input"))
    )
    (net (code "21") (name "/QDR2.A18") (class "Default")
      (node (ref "RP19") (pin "3") (pinfunction "3_3") (pintype "passive"))
      (node (ref "U60") (pin "A3") (pinfunction "A18_A3") (pintype "input"))
    )
    (net (code "22") (name "/QDR2.A19") (class "Default")
      (node (ref "RP24") (pin "1") (pinfunction "1_1") (pintype "passive"))
      (node (ref "U60") (pin "A10") (pinfunction "A19_A10") (pintype "input"))
    )
    (net (code "23") (name "/QDR2.A20") (class "Default")
      (node (ref "RP19") (pin "4") (pinfunction "4_4") (pintype "passive"))
      (node (ref "U60") (pin "A2") (pinfunction "A20_A2") (pintype "input"))
    )
    (net (code "25") (name "/QDR2.BWn0") (class "Default")
      (node (ref "R309") (pin "1") (pinfunction "1_1") (pintype "passive"))
      (node (ref "U60") (pin "B7") (pinfunction "BWS#0_B7") (pintype "input"))
    )
    (net (code "26") (name "/QDR2.BWn1") (class "Default")
      (node (ref "R310") (pin "1") (pinfunction "1_1") (pintype "passive"))
      (node (ref "U60") (pin "A7") (pinfunction "BWS#1_A7") (pintype "input"))
    )
    (net (code "27") (name "/QDR2.BWn2") (class "Default")
      (node (ref "R311") (pin "1") (pinfunction "1_1") (pintype "passive"))
      (node (ref "U60") (pin "A5") (pinfunction "BWS#2_A5") (pintype "input"))
    )
    (net (code "28") (name "/QDR2.BWn3") (class "Default")
      (node (ref "R312") (pin "1") (pinfunction "1_1") (pintype "passive"))
      (node (ref "U60") (pin "B5") (pinfunction "BWS#3_B5") (pintype "input"))
    )
    (net (code "29") (name "/QDR2.D0") (class "Default")
      (node (ref "U60") (pin "P10") (pinfunction "D0_P10") (pintype "input"))
    )
    (net (code "30") (name "/QDR2.D1") (class "Default")
      (node (ref "U60") (pin "N11") (pinfunction "D1_N11") (pintype "input"))
    )
    (net (code "31") (name "/QDR2.D2") (class "Default")
      (node (ref "U60") (pin "M11") (pinfunction "D2_M11") (pintype "input"))
    )
    (net (code "32") (name "/QDR2.D3") (class "Default")
      (node (ref "U60") (pin "K10") (pinfunction "D3_K10") (pintype "input"))
    )
    (net (code "33") (name "/QDR2.D4") (class "Default")
      (node (ref "U60") (pin "J11") (pinfunction "D4_J11") (pintype "input"))
    )
    (net (code "34") (name "/QDR2.D5") (class "Default")
      (node (ref "U60") (pin "G11") (pinfunction "D5_G11") (pintype "input"))
    )
    (net (code "35") (name "/QDR2.D6") (class "Default")
      (node (ref "U60") (pin "E10") (pinfunction "D6_E10") (pintype "input"))
    )
    (net (code "36") (name "/QDR2.D7") (class "Default")
      (node (ref "U60") (pin "D11") (pinfunction "D7_D11") (pintype "input"))
    )
    (net (code "37") (name "/QDR2.D8") (class "Default")
      (node (ref "U60") (pin "C11") (pinfunction "D8_C11") (pintype "input"))
    )
    (net (code "38") (name "/QDR2.D9") (class "Default")
      (node (ref "U60") (pin "N10") (pinfunction "D9_N10") (pintype "input"))
    )
    (net (code "39") (name "/QDR2.D10") (class "Default")
      (node (ref "U60") (pin "M9") (pinfunction "D10_M9") (pintype "input"))
    )
    (net (code "40") (name "/QDR2.D11") (class "Default")
      (node (ref "U60") (pin "L9") (pinfunction "D11_L9") (pintype "input"))
    )
    (net (code "41") (name "/QDR2.D12") (class "Default")
      (node (ref "U60") (pin "J9") (pinfunction "D12_J9") (pintype "input"))
    )
    (net (code "42") (name "/QDR2.D13") (class "Default")
      (node (ref "U60") (pin "G10") (pinfunction "D13_G10") (pintype "input"))
    )
    (net (code "43") (name "/QDR2.D14") (class "Default")
      (node (ref "U60") (pin "F9") (pinfunction "D14_F9") (pintype "input"))
    )
    (net (code "44") (name "/QDR2.D15") (class "Default")
      (node (ref "U60") (pin "D10") (pinfunction "D15_D10") (pintype "input"))
    )
    (net (code "45") (name "/QDR2.D16") (class "Default")
      (node (ref "U60") (pin "C9") (pinfunction "D16_C9") (pintype "input"))
    )
    (net (code "46") (name "/QDR2.D17") (class "Default")
      (node (ref "U60") (pin "B9") (pinfunction "D17_B9") (pintype "input"))
    )
    (net (code "47") (name "/QDR2.D18") (class "Default")
      (node (ref "U60") (pin "B3") (pinfunction "D18_B3") (pintype "input"))
    )
    (net (code "48") (name "/QDR2.D19") (class "Default")
      (node (ref "U60") (pin "C3") (pinfunction "D19_C3") (pintype "input"))
    )
    (net (code "49") (name "/QDR2.D20") (class "Default")
      (node (ref "U60") (pin "D2") (pinfunction "D20_D2") (pintype "input"))
    )
    (net (code "50") (name "/QDR2.D21") (class "Default")
      (node (ref "U60") (pin "F3") (pinfunction "D21_F3") (pintype "input"))
    )
    (net (code "51") (name "/QDR2.D22") (class "Default")
      (node (ref "U60") (pin "G2") (pinfunction "D22_G2") (pintype "input"))
    )
    (net (code "52") (name "/QDR2.D23") (class "Default")
      (node (ref "U60") (pin "J3") (pinfunction "D23_J3") (pintype "input"))
    )
    (net (code "53") (name "/QDR2.D24") (class "Default")
      (node (ref "U60") (pin "L3") (pinfunction "D24_L3") (pintype "input"))
    )
    (net (code "54") (name "/QDR2.D25") (class "Default")
      (node (ref "U60") (pin "M3") (pinfunction "D25_M3") (pintype "input"))
    )
    (net (code "55") (name "/QDR2.D26") (class "Default")
      (node (ref "U60") (pin "N2") (pinfunction "D26_N2") (pintype "input"))
    )
    (net (code "56") (name "/QDR2.D27") (class "Default")
      (node (ref "U60") (pin "C1") (pinfunction "D27_C1") (pintype "input"))
    )
    (net (code "57") (name "/QDR2.D28") (class "Default")
      (node (ref "U60") (pin "D1") (pinfunction "D28_D1") (pintype "input"))
    )
    (net (code "58") (name "/QDR2.D29") (class "Default")
      (node (ref "U60") (pin "E2") (pinfunction "D29_E2") (pintype "input"))
    )
    (net (code "59") (name "/QDR2.D30") (class "Default")
      (node (ref "U60") (pin "G1") (pinfunction "D30_G1") (pintype "input"))
    )
    (net (code "60") (name "/QDR2.D31") (class "Default")
      (node (ref "U60") (pin "J1") (pinfunction "D31_J1") (pintype "input"))
    )
    (net (code "61") (name "/QDR2.D32") (class "Default")
      (node (ref "U60") (pin "K2") (pinfunction "D32_K2") (pintype "input"))
    )
    (net (code "62") (name "/QDR2.D33") (class "Default")
      (node (ref "U60") (pin "M1") (pinfunction "D33_M1") (pintype "input"))
    )
    (net (code "63") (name "/QDR2.D34") (class "Default")
      (node (ref "U60") (pin "N1") (pinfunction "D34_N1") (pintype "input"))
    )
    (net (code "64") (name "/QDR2.D35") (class "Default")
      (node (ref "U60") (pin "P2") (pinfunction "D35_P2") (pintype "input"))
    )
    (net (code "65") (name "/QDR2.DOFFn") (class "Default")
      (node (ref "U60") (pin "H1") (pinfunction "DOFF#_H1") (pintype "input"))
    )
    (net (code "67") (name "/QDR2.K") (class "Default")
      (node (ref "U60") (pin "B6") (pinfunction "K_B6") (pintype "input"))
    )
    (net (code "68") (name "/QDR2.Kn") (class "Default")
      (node (ref "U60") (pin "A6") (pinfunction "K#_A6") (pintype "input"))
    )
    (net (code "69") (name "/QDR2.Q0") (class "Default")
      (node (ref "U60") (pin "P11") (pinfunction "Q0_P11") (pintype "output"))
    )
    (net (code "70") (name "/QDR2.Q1") (class "Default")
      (node (ref "U60") (pin "M10") (pinfunction "Q1_M10") (pintype "output"))
    )
    (net (code "71") (name "/QDR2.Q2") (class "Default")
      (node (ref "U60") (pin "L11") (pinfunction "Q2_L11") (pintype "output"))
    )
    (net (code "72") (name "/QDR2.Q3") (class "Default")
      (node (ref "U60") (pin "K11") (pinfunction "Q3_K11") (pintype "output"))
    )
    (net (code "73") (name "/QDR2.Q4") (class "Default")
      (node (ref "U60") (pin "J10") (pinfunction "Q4_J10") (pintype "output"))
    )
    (net (code "74") (name "/QDR2.Q5") (class "Default")
      (node (ref "U60") (pin "F11") (pinfunction "Q5_F11") (pintype "output"))
    )
    (net (code "75") (name "/QDR2.Q6") (class "Default")
      (node (ref "U60") (pin "E11") (pinfunction "Q6_E11") (pintype "output"))
    )
    (net (code "76") (name "/QDR2.Q7") (class "Default")
      (node (ref "U60") (pin "C10") (pinfunction "Q7_C10") (pintype "output"))
    )
    (net (code "77") (name "/QDR2.Q8") (class "Default")
      (node (ref "U60") (pin "B11") (pinfunction "Q8_B11") (pintype "output"))
    )
    (net (code "78") (name "/QDR2.Q9") (class "Default")
      (node (ref "U60") (pin "P9") (pinfunction "Q9_P9") (pintype "output"))
    )
    (net (code "79") (name "/QDR2.Q10") (class "Default")
      (node (ref "U60") (pin "N9") (pinfunction "Q10_N9") (pintype "output"))
    )
    (net (code "80") (name "/QDR2.Q11") (class "Default")
      (node (ref "U60") (pin "L10") (pinfunction "Q11_L10") (pintype "output"))
    )
    (net (code "81") (name "/QDR2.Q12") (class "Default")
      (node (ref "U60") (pin "K9") (pinfunction "Q12_K9") (pintype "output"))
    )
    (net (code "82") (name "/QDR2.Q13") (class "Default")
      (node (ref "U60") (pin "G9") (pinfunction "Q13_G9") (pintype "output"))
    )
    (net (code "83") (name "/QDR2.Q14") (class "Default")
      (node (ref "U60") (pin "F10") (pinfunction "Q14_F10") (pintype "output"))
    )
    (net (code "84") (name "/QDR2.Q15") (class "Default")
      (node (ref "U60") (pin "E9") (pinfunction "Q15_E9") (pintype "output"))
    )
    (net (code "85") (name "/QDR2.Q16") (class "Default")
      (node (ref "U60") (pin "D9") (pinfunction "Q16_D9") (pintype "output"))
    )
    (net (code "86") (name "/QDR2.Q17") (class "Default")
      (node (ref "U60") (pin "B10") (pinfunction "Q17_B10") (pintype "output"))
    )
    (net (code "87") (name "/QDR2.Q18") (class "Default")
      (node (ref "U60") (pin "B2") (pinfunction "Q18_B2") (pintype "output"))
    )
    (net (code "88") (name "/QDR2.Q19") (class "Default")
      (node (ref "U60") (pin "D3") (pinfunction "Q19_D3") (pintype "output"))
    )
    (net (code "89") (name "/QDR2.Q20") (class "Default")
      (node (ref "U60") (pin "E3") (pinfunction "Q20_E3") (pintype "output"))
    )
    (net (code "90") (name "/QDR2.Q21") (class "Default")
      (node (ref "U60") (pin "F2") (pinfunction "Q21_F2") (pintype "output"))
    )
    (net (code "91") (name "/QDR2.Q22") (class "Default")
      (node (ref "U60") (pin "G3") (pinfunction "Q22_G3") (pintype "output"))
    )
    (net (code "92") (name "/QDR2.Q23") (class "Default")
      (node (ref "U60") (pin "K3") (pinfunction "Q23_K3") (pintype "output"))
    )
    (net (code "93") (name "/QDR2.Q24") (class "Default")
      (node (ref "U60") (pin "L2") (pinfunction "Q24_L2") (pintype "output"))
    )
    (net (code "94") (name "/QDR2.Q25") (class "Default")
      (node (ref "U60") (pin "N3") (pinfunction "Q25_N3") (pintype "output"))
    )
    (net (code "95") (name "/QDR2.Q26") (class "Default")
      (node (ref "U60") (pin "P3") (pinfunction "Q26_P3") (pintype "output"))
    )
    (net (code "96") (name "/QDR2.Q27") (class "Default")
      (node (ref "U60") (pin "B1") (pinfunction "Q27_B1") (pintype "output"))
    )
    (net (code "97") (name "/QDR2.Q28") (class "Default")
      (node (ref "U60") (pin "C2") (pinfunction "Q28_C2") (pintype "output"))
    )
    (net (code "98") (name "/QDR2.Q29") (class "Default")
      (node (ref "U60") (pin "E1") (pinfunction "Q29_E1") (pintype "output"))
    )
    (net (code "99") (name "/QDR2.Q30") (class "Default")
      (node (ref "U60") (pin "F1") (pinfunction "Q30_F1") (pintype "output"))
    )
    (net (code "100") (name "/QDR2.Q31") (class "Default")
      (node (ref "U60") (pin "J2") (pinfunction "Q31_J2") (pintype "output"))
    )
    (net (code "101") (name "/QDR2.Q32") (class "Default")
      (node (ref "U60") (pin "K1") (pinfunction "Q32_K1") (pintype "output"))
    )
    (net (code "102") (name "/QDR2.Q33") (class "Default")
      (node (ref "U60") (pin "L1") (pinfunction "Q33_L1") (pintype "output"))
    )
    (net (code "103") (name "/QDR2.Q34") (class "Default")
      (node (ref "U60") (pin "M2") (pinfunction "Q34_M2") (pintype "output"))
    )
    (net (code "104") (name "/QDR2.Q35") (class "Default")
      (node (ref "U60") (pin "P1") (pinfunction "Q35_P1") (pintype "output"))
    )
    (net (code "106") (name "/QDR2.RDn") (class "Default")
      (node (ref "RP24") (pin "4") (pinfunction "4_4") (pintype "passive"))
      (node (ref "U60") (pin "A8") (pinfunction "RPS#_A8") (pintype "input"))
    )
    (net (code "107") (name "/QDR2.WRn") (class "Default")
      (node (ref "RP19") (pin "2") (pinfunction "2_2") (pintype "passive"))
      (node (ref "U60") (pin "A4") (pinfunction "WPS#_A4") (pintype "input"))
    )
    (net (code "108") (name "/QDR2_TCK") (class "Default")
      (node (ref "U60") (pin "R2") (pinfunction "TCK_R2") (pintype "input"))
    )
    (net (code "109") (name "/QDR2_TDI") (class "Default")
      (node (ref "U60") (pin "R11") (pinfunction "TDI_R11") (pintype "input"))
    )
    (net (code "110") (name "/QDR2_TDO") (class "Default")
      (node (ref "U60") (pin "R1") (pinfunction "TDO_R1") (pintype "output"))
    )
    (net (code "111") (name "/QDR2_TMS") (class "Default")
      (node (ref "U60") (pin "R10") (pinfunction "TMS_R10") (pintype "input"))
    )
    (net (code "113") (name "/QDR3.A0") (class "Default")
      (node (ref "RP22") (pin "1") (pinfunction "1_1") (pintype "passive"))
      (node (ref "U61") (pin "B4") (pinfunction "A0_B4") (pintype "input"))
    )
    (net (code "114") (name "/QDR3.A1") (class "Default")
      (node (ref "RP26") (pin "3") (pinfunction "3_3") (pintype "passive"))
      (node (ref "U61") (pin "B8") (pinfunction "A1_B8") (pintype "input"))
    )
    (net (code "115") (name "/QDR3.A2") (class "Default")
      (node (ref "R283") (pin "1") (pinfunction "1_1") (pintype "passive"))
      (node (ref "U61") (pin "C5") (pinfunction "A2_C5") (pintype "input"))
    )
    (net (code "116") (name "/QDR3.A3") (class "Default")
      (node (ref "R281") (pin "1") (pinfunction "1_1") (pintype "passive"))
      (node (ref "U61") (pin "C7") (pinfunction "A3_C7") (pintype "input"))
    )
    (net (code "117") (name "/QDR3.A4") (class "Default")
      (node (ref "RP25") (pin "2") (pinfunction "2_2") (pintype "passive"))
      (node (ref "U61") (pin "N5") (pinfunction "A4_N5") (pintype "input"))
    )
    (net (code "118") (name "/QDR3.A5") (class "Default")
      (node (ref "RP25") (pin "3") (pinfunction "3_3") (pintype "passive"))
      (node (ref "U61") (pin "N6") (pinfunction "A5_N6") (pintype "input"))
    )
    (net (code "119") (name "/QDR3.A6") (class "Default")
      (node (ref "RP25") (pin "4") (pinfunction "4_4") (pintype "passive"))
      (node (ref "U61") (pin "N7") (pinfunction "A6_N7") (pintype "input"))
    )
    (net (code "120") (name "/QDR3.A7") (class "Default")
      (node (ref "RP21") (pin "2") (pinfunction "2_2") (pintype "passive"))
      (node (ref "U61") (pin "P4") (pinfunction "A7_P4") (pintype "input"))
    )
    (net (code "121") (name "/QDR3.A8") (class "Default")
      (node (ref "RP21") (pin "4") (pinfunction "4_4") (pintype "passive"))
      (node (ref "U61") (pin "P5") (pinfunction "A8_P5") (pintype "input"))
    )
    (net (code "122") (name "/QDR3.A9") (class "Default")
      (node (ref "RP20") (pin "1") (pinfunction "1_1") (pintype "passive"))
      (node (ref "U61") (pin "P7") (pinfunction "A9_P7") (pintype "input"))
    )
    (net (code "123") (name "/QDR3.A10") (class "Default")
      (node (ref "RP20") (pin "3") (pinfunction "3_3") (pintype "passive"))
      (node (ref "U61") (pin "P8") (pinfunction "A10_P8") (pintype "input"))
    )
    (net (code "124") (name "/QDR3.A11") (class "Default")
      (node (ref "RP26") (pin "2") (pinfunction "2_2") (pintype "passive"))
      (node (ref "U61") (pin "A9") (pinfunction "A11_A9") (pintype "input"))
    )
    (net (code "125") (name "/QDR3.A12") (class "Default")
      (node (ref "RP21") (pin "1") (pinfunction "1_1") (pintype "passive"))
      (node (ref "U61") (pin "R3") (pinfunction "A12_R3") (pintype "input"))
    )
    (net (code "126") (name "/QDR3.A13") (class "Default")
      (node (ref "RP21") (pin "3") (pinfunction "3_3") (pintype "passive"))
      (node (ref "U61") (pin "R4") (pinfunction "A13_R4") (pintype "input"))
    )
    (net (code "127") (name "/QDR3.A14") (class "Default")
      (node (ref "RP25") (pin "1") (pinfunction "1_1") (pintype "passive"))
      (node (ref "U61") (pin "R5") (pinfunction "A14_R5") (pintype "input"))
    )
    (net (code "128") (name "/QDR3.A15") (class "Default")
      (node (ref "R279") (pin "1") (pinfunction "1_1") (pintype "passive"))
      (node (ref "U61") (pin "R7") (pinfunction "A15_R7") (pintype "input"))
    )
    (net (code "129") (name "/QDR3.A16") (class "Default")
      (node (ref "RP20") (pin "2") (pinfunction "2_2") (pintype "passive"))
      (node (ref "U61") (pin "R8") (pinfunction "A16_R8") (pintype "input"))
    )
    (net (code "130") (name "/QDR3.A17") (class "Default")
      (node (ref "RP20") (pin "4") (pinfunction "4_4") (pintype "passive"))
      (node (ref "U61") (pin "R9") (pinfunction "A17_R9") (pintype "input"))
    )
    (net (code "131") (name "/QDR3.A18") (class "Default")
      (node (ref "RP22") (pin "3") (pinfunction "3_3") (pintype "passive"))
      (node (ref "U61") (pin "A3") (pinfunction "A18_A3") (pintype "input"))
    )
    (net (code "132") (name "/QDR3.A19") (class "Default")
      (node (ref "RP26") (pin "1") (pinfunction "1_1") (pintype "passive"))
      (node (ref "U61") (pin "A10") (pinfunction "A19_A10") (pintype "input"))
    )
    (net (code "133") (name "/QDR3.A20") (class "Default")
      (node (ref "RP22") (pin "4") (pinfunction "4_4") (pintype "passive"))
      (node (ref "U61") (pin "A2") (pinfunction "A20_A2") (pintype "input"))
    )
    (net (code "135") (name "/QDR3.BWn0") (class "Default")
      (node (ref "R313") (pin "1") (pinfunction "1_1") (pintype "passive"))
      (node (ref "U61") (pin "B7") (pinfunction "BWS#0_B7") (pintype "input"))
    )
    (net (code "136") (name "/QDR3.BWn1") (class "Default")
      (node (ref "R314") (pin "1") (pinfunction "1_1") (pintype "passive"))
      (node (ref "U61") (pin "A7") (pinfunction "BWS#1_A7") (pintype "input"))
    )
    (net (code "137") (name "/QDR3.BWn2") (class "Default")
      (node (ref "R315") (pin "1") (pinfunction "1_1") (pintype "passive"))
      (node (ref "U61") (pin "A5") (pinfunction "BWS#2_A5") (pintype "input"))
    )
    (net (code "138") (name "/QDR3.BWn3") (class "Default")
      (node (ref "R316") (pin "1") (pinfunction "1_1") (pintype "passive"))
      (node (ref "U61") (pin "B5") (pinfunction "BWS#3_B5") (pintype "input"))
    )
    (net (code "139") (name "/QDR3.D0") (class "Default")
      (node (ref "U61") (pin "P10") (pinfunction "D0_P10") (pintype "input"))
    )
    (net (code "140") (name "/QDR3.D1") (class "Default")
      (node (ref "U61") (pin "N11") (pinfunction "D1_N11") (pintype "input"))
    )
    (net (code "141") (name "/QDR3.D2") (class "Default")
      (node (ref "U61") (pin "M11") (pinfunction "D2_M11") (pintype "input"))
    )
    (net (code "142") (name "/QDR3.D3") (class "Default")
      (node (ref "U61") (pin "K10") (pinfunction "D3_K10") (pintype "input"))
    )
    (net (code "143") (name "/QDR3.D4") (class "Default")
      (node (ref "U61") (pin "J11") (pinfunction "D4_J11") (pintype "input"))
    )
    (net (code "144") (name "/QDR3.D5") (class "Default")
      (node (ref "U61") (pin "G11") (pinfunction "D5_G11") (pintype "input"))
    )
    (net (code "145") (name "/QDR3.D6") (class "Default")
      (node (ref "U61") (pin "E10") (pinfunction "D6_E10") (pintype "input"))
    )
    (net (code "146") (name "/QDR3.D7") (class "Default")
      (node (ref "U61") (pin "D11") (pinfunction "D7_D11") (pintype "input"))
    )
    (net (code "147") (name "/QDR3.D8") (class "Default")
      (node (ref "U61") (pin "C11") (pinfunction "D8_C11") (pintype "input"))
    )
    (net (code "148") (name "/QDR3.D9") (class "Default")
      (node (ref "U61") (pin "N10") (pinfunction "D9_N10") (pintype "input"))
    )
    (net (code "149") (name "/QDR3.D10") (class "Default")
      (node (ref "U61") (pin "M9") (pinfunction "D10_M9") (pintype "input"))
    )
    (net (code "150") (name "/QDR3.D11") (class "Default")
      (node (ref "U61") (pin "L9") (pinfunction "D11_L9") (pintype "input"))
    )
    (net (code "151") (name "/QDR3.D12") (class "Default")
      (node (ref "U61") (pin "J9") (pinfunction "D12_J9") (pintype "input"))
    )
    (net (code "152") (name "/QDR3.D13") (class "Default")
      (node (ref "U61") (pin "G10") (pinfunction "D13_G10") (pintype "input"))
    )
    (net (code "153") (name "/QDR3.D14") (class "Default")
      (node (ref "U61") (pin "F9") (pinfunction "D14_F9") (pintype "input"))
    )
    (net (code "154") (name "/QDR3.D15") (class "Default")
      (node (ref "U61") (pin "D10") (pinfunction "D15_D10") (pintype "input"))
    )
    (net (code "155") (name "/QDR3.D16") (class "Default")
      (node (ref "U61") (pin "C9") (pinfunction "D16_C9") (pintype "input"))
    )
    (net (code "156") (name "/QDR3.D17") (class "Default")
      (node (ref "U61") (pin "B9") (pinfunction "D17_B9") (pintype "input"))
    )
    (net (code "157") (name "/QDR3.D18") (class "Default")
      (node (ref "U61") (pin "B3") (pinfunction "D18_B3") (pintype "input"))
    )
    (net (code "158") (name "/QDR3.D19") (class "Default")
      (node (ref "U61") (pin "C3") (pinfunction "D19_C3") (pintype "input"))
    )
    (net (code "159") (name "/QDR3.D20") (class "Default")
      (node (ref "U61") (pin "D2") (pinfunction "D20_D2") (pintype "input"))
    )
    (net (code "160") (name "/QDR3.D21") (class "Default")
      (node (ref "U61") (pin "F3") (pinfunction "D21_F3") (pintype "input"))
    )
    (net (code "161") (name "/QDR3.D22") (class "Default")
      (node (ref "U61") (pin "G2") (pinfunction "D22_G2") (pintype "input"))
    )
    (net (code "162") (name "/QDR3.D23") (class "Default")
      (node (ref "U61") (pin "J3") (pinfunction "D23_J3") (pintype "input"))
    )
    (net (code "163") (name "/QDR3.D24") (class "Default")
      (node (ref "U61") (pin "L3") (pinfunction "D24_L3") (pintype "input"))
    )
    (net (code "164") (name "/QDR3.D25") (class "Default")
      (node (ref "U61") (pin "M3") (pinfunction "D25_M3") (pintype "input"))
    )
    (net (code "165") (name "/QDR3.D26") (class "Default")
      (node (ref "U61") (pin "N2") (pinfunction "D26_N2") (pintype "input"))
    )
    (net (code "166") (name "/QDR3.D27") (class "Default")
      (node (ref "U61") (pin "C1") (pinfunction "D27_C1") (pintype "input"))
    )
    (net (code "167") (name "/QDR3.D28") (class "Default")
      (node (ref "U61") (pin "D1") (pinfunction "D28_D1") (pintype "input"))
    )
    (net (code "168") (name "/QDR3.D29") (class "Default")
      (node (ref "U61") (pin "E2") (pinfunction "D29_E2") (pintype "input"))
    )
    (net (code "169") (name "/QDR3.D30") (class "Default")
      (node (ref "U61") (pin "G1") (pinfunction "D30_G1") (pintype "input"))
    )
    (net (code "170") (name "/QDR3.D31") (class "Default")
      (node (ref "U61") (pin "J1") (pinfunction "D31_J1") (pintype "input"))
    )
    (net (code "171") (name "/QDR3.D32") (class "Default")
      (node (ref "U61") (pin "K2") (pinfunction "D32_K2") (pintype "input"))
    )
    (net (code "172") (name "/QDR3.D33") (class "Default")
      (node (ref "U61") (pin "M1") (pinfunction "D33_M1") (pintype "input"))
    )
    (net (code "173") (name "/QDR3.D34") (class "Default")
      (node (ref "U61") (pin "N1") (pinfunction "D34_N1") (pintype "input"))
    )
    (net (code "174") (name "/QDR3.D35") (class "Default")
      (node (ref "U61") (pin "P2") (pinfunction "D35_P2") (pintype "input"))
    )
    (net (code "175") (name "/QDR3.DOFFn") (class "Default")
      (node (ref "U61") (pin "H1") (pinfunction "DOFF#_H1") (pintype "input"))
    )
    (net (code "177") (name "/QDR3.K") (class "Default")
      (node (ref "U61") (pin "B6") (pinfunction "K_B6") (pintype "input"))
    )
    (net (code "178") (name "/QDR3.Kn") (class "Default")
      (node (ref "U61") (pin "A6") (pinfunction "K#_A6") (pintype "input"))
    )
    (net (code "179") (name "/QDR3.Q0") (class "Default")
      (node (ref "U61") (pin "P11") (pinfunction "Q0_P11") (pintype "output"))
    )
    (net (code "180") (name "/QDR3.Q1") (class "Default")
      (node (ref "U61") (pin "M10") (pinfunction "Q1_M10") (pintype "output"))
    )
    (net (code "181") (name "/QDR3.Q2") (class "Default")
      (node (ref "U61") (pin "L11") (pinfunction "Q2_L11") (pintype "output"))
    )
    (net (code "182") (name "/QDR3.Q3") (class "Default")
      (node (ref "U61") (pin "K11") (pinfunction "Q3_K11") (pintype "output"))
    )
    (net (code "183") (name "/QDR3.Q4") (class "Default")
      (node (ref "U61") (pin "J10") (pinfunction "Q4_J10") (pintype "output"))
    )
    (net (code "184") (name "/QDR3.Q5") (class "Default")
      (node (ref "U61") (pin "F11") (pinfunction "Q5_F11") (pintype "output"))
    )
    (net (code "185") (name "/QDR3.Q6") (class "Default")
      (node (ref "U61") (pin "E11") (pinfunction "Q6_E11") (pintype "output"))
    )
    (net (code "186") (name "/QDR3.Q7") (class "Default")
      (node (ref "U61") (pin "C10") (pinfunction "Q7_C10") (pintype "output"))
    )
    (net (code "187") (name "/QDR3.Q8") (class "Default")
      (node (ref "U61") (pin "B11") (pinfunction "Q8_B11") (pintype "output"))
    )
    (net (code "188") (name "/QDR3.Q9") (class "Default")
      (node (ref "U61") (pin "P9") (pinfunction "Q9_P9") (pintype "output"))
    )
    (net (code "189") (name "/QDR3.Q10") (class "Default")
      (node (ref "U61") (pin "N9") (pinfunction "Q10_N9") (pintype "output"))
    )
    (net (code "190") (name "/QDR3.Q11") (class "Default")
      (node (ref "U61") (pin "L10") (pinfunction "Q11_L10") (pintype "output"))
    )
    (net (code "191") (name "/QDR3.Q12") (class "Default")
      (node (ref "U61") (pin "K9") (pinfunction "Q12_K9") (pintype "output"))
    )
    (net (code "192") (name "/QDR3.Q13") (class "Default")
      (node (ref "U61") (pin "G9") (pinfunction "Q13_G9") (pintype "output"))
    )
    (net (code "193") (name "/QDR3.Q14") (class "Default")
      (node (ref "U61") (pin "F10") (pinfunction "Q14_F10") (pintype "output"))
    )
    (net (code "194") (name "/QDR3.Q15") (class "Default")
      (node (ref "U61") (pin "E9") (pinfunction "Q15_E9") (pintype "output"))
    )
    (net (code "195") (name "/QDR3.Q16") (class "Default")
      (node (ref "U61") (pin "D9") (pinfunction "Q16_D9") (pintype "output"))
    )
    (net (code "196") (name "/QDR3.Q17") (class "Default")
      (node (ref "U61") (pin "B10") (pinfunction "Q17_B10") (pintype "output"))
    )
    (net (code "197") (name "/QDR3.Q18") (class "Default")
      (node (ref "U61") (pin "B2") (pinfunction "Q18_B2") (pintype "output"))
    )
    (net (code "198") (name "/QDR3.Q19") (class "Default")
      (node (ref "U61") (pin "D3") (pinfunction "Q19_D3") (pintype "output"))
    )
    (net (code "199") (name "/QDR3.Q20") (class "Default")
      (node (ref "U61") (pin "E3") (pinfunction "Q20_E3") (pintype "output"))
    )
    (net (code "200") (name "/QDR3.Q21") (class "Default")
      (node (ref "U61") (pin "F2") (pinfunction "Q21_F2") (pintype "output"))
    )
    (net (code "201") (name "/QDR3.Q22") (class "Default")
      (node (ref "U61") (pin "G3") (pinfunction "Q22_G3") (pintype "output"))
    )
    (net (code "202") (name "/QDR3.Q23") (class "Default")
      (node (ref "U61") (pin "K3") (pinfunction "Q23_K3") (pintype "output"))
    )
    (net (code "203") (name "/QDR3.Q24") (class "Default")
      (node (ref "U61") (pin "L2") (pinfunction "Q24_L2") (pintype "output"))
    )
    (net (code "204") (name "/QDR3.Q25") (class "Default")
      (node (ref "U61") (pin "N3") (pinfunction "Q25_N3") (pintype "output"))
    )
    (net (code "205") (name "/QDR3.Q26") (class "Default")
      (node (ref "U61") (pin "P3") (pinfunction "Q26_P3") (pintype "output"))
    )
    (net (code "206") (name "/QDR3.Q27") (class "Default")
      (node (ref "U61") (pin "B1") (pinfunction "Q27_B1") (pintype "output"))
    )
    (net (code "207") (name "/QDR3.Q28") (class "Default")
      (node (ref "U61") (pin "C2") (pinfunction "Q28_C2") (pintype "output"))
    )
    (net (code "208") (name "/QDR3.Q29") (class "Default")
      (node (ref "U61") (pin "E1") (pinfunction "Q29_E1") (pintype "output"))
    )
    (net (code "209") (name "/QDR3.Q30") (class "Default")
      (node (ref "U61") (pin "F1") (pinfunction "Q30_F1") (pintype "output"))
    )
    (net (code "210") (name "/QDR3.Q31") (class "Default")
      (node (ref "U61") (pin "J2") (pinfunction "Q31_J2") (pintype "output"))
    )
    (net (code "211") (name "/QDR3.Q32") (class "Default")
      (node (ref "U61") (pin "K1") (pinfunction "Q32_K1") (pintype "output"))
    )
    (net (code "212") (name "/QDR3.Q33") (class "Default")
      (node (ref "U61") (pin "L1") (pinfunction "Q33_L1") (pintype "output"))
    )
    (net (code "213") (name "/QDR3.Q34") (class "Default")
      (node (ref "U61") (pin "M2") (pinfunction "Q34_M2") (pintype "output"))
    )
    (net (code "214") (name "/QDR3.Q35") (class "Default")
      (node (ref "U61") (pin "P1") (pinfunction "Q35_P1") (pintype "output"))
    )
    (net (code "216") (name "/QDR3.RDn") (class "Default")
      (node (ref "RP26") (pin "4") (pinfunction "4_4") (pintype "passive"))
      (node (ref "U61") (pin "A8") (pinfunction "RPS#_A8") (pintype "input"))
    )
    (net (code "217") (name "/QDR3.WRn") (class "Default")
      (node (ref "RP22") (pin "2") (pinfunction "2_2") (pintype "passive"))
      (node (ref "U61") (pin "A4") (pinfunction "WPS#_A4") (pintype "input"))
    )
    (net (code "218") (name "/QDR3_TCK") (class "Default")
      (node (ref "U61") (pin "R2") (pinfunction "TCK_R2") (pintype "input"))
    )
    (net (code "219") (name "/QDR3_TDI") (class "Default")
      (node (ref "U61") (pin "R11") (pinfunction "TDI_R11") (pintype "input"))
    )
    (net (code "220") (name "/QDR3_TDO") (class "Default")
      (node (ref "U61") (pin "R1") (pinfunction "TDO_R1") (pintype "output"))
    )
    (net (code "221") (name "/QDR3_TMS") (class "Default")
      (node (ref "U61") (pin "R10") (pinfunction "TMS_R10") (pintype "input"))
    )
    (net (code "225") (name "1V5") (class "Default")
      (node (ref "C572") (pin "2") (pinfunction "2_2") (pintype "passive"))
      (node (ref "C573") (pin "2") (pinfunction "2_2") (pintype "passive"))
      (node (ref "C574") (pin "2") (pinfunction "2_2") (pintype "passive"))
      (node (ref "C575") (pin "2") (pinfunction "2_2") (pintype "passive"))
      (node (ref "C576") (pin "2") (pinfunction "2_2") (pintype "passive"))
      (node (ref "C577") (pin "2") (pinfunction "2_2") (pintype "passive"))
      (node (ref "C578") (pin "2") (pinfunction "2_2") (pintype "passive"))
      (node (ref "C579") (pin "2") (pinfunction "2_2") (pintype "passive"))
      (node (ref "C580") (pin "2") (pinfunction "2_2") (pintype "passive"))
      (node (ref "C582") (pin "2") (pinfunction "2_2") (pintype "passive"))
      (node (ref "C583") (pin "2") (pinfunction "2_2") (pintype "passive"))
      (node (ref "C584") (pin "2") (pinfunction "2_2") (pintype "passive"))
      (node (ref "C585") (pin "2") (pinfunction "2_2") (pintype "passive"))
      (node (ref "C586") (pin "2") (pinfunction "2_2") (pintype "passive"))
      (node (ref "C587") (pin "2") (pinfunction "2_2") (pintype "passive"))
      (node (ref "C588") (pin "2") (pinfunction "2_2") (pintype "passive"))
      (node (ref "C589") (pin "2") (pinfunction "2_2") (pintype "passive"))
      (node (ref "C590") (pin "2") (pinfunction "2_2") (pintype "passive"))
      (node (ref "C627") (pin "2") (pinfunction "2_2") (pintype "passive"))
      (node (ref "U60") (pin "E4") (pinfunction "VDDQ0_E4") (pintype "power_in"))
      (node (ref "U60") (pin "E8") (pinfunction "VDDQ1_E8") (pintype "power_in"))
      (node (ref "U60") (pin "F4") (pinfunction "VDDQ2_F4") (pintype "power_in"))
      (node (ref "U60") (pin "F8") (pinfunction "VDDQ3_F8") (pintype "power_in"))
      (node (ref "U60") (pin "G4") (pinfunction "VDDQ4_G4") (pintype "power_in"))
      (node (ref "U60") (pin "G8") (pinfunction "VDDQ5_G8") (pintype "power_in"))
      (node (ref "U60") (pin "H3") (pinfunction "VDDQ6_H3") (pintype "power_in"))
      (node (ref "U60") (pin "H4") (pinfunction "VDDQ7_H4") (pintype "power_in"))
      (node (ref "U60") (pin "H8") (pinfunction "VDDQ8_H8") (pintype "power_in"))
      (node (ref "U60") (pin "H9") (pinfunction "VDDQ9_H9") (pintype "power_in"))
      (node (ref "U60") (pin "J4") (pinfunction "VDDQ10_J4") (pintype "power_in"))
      (node (ref "U60") (pin "J8") (pinfunction "VDDQ11_J8") (pintype "power_in"))
      (node (ref "U60") (pin "K4") (pinfunction "VDDQ12_K4") (pintype "power_in"))
      (node (ref "U60") (pin "K8") (pinfunction "VDDQ13_K8") (pintype "power_in"))
      (node (ref "U60") (pin "L4") (pinfunction "VDDQ14_L4") (pintype "power_in"))
      (node (ref "U60") (pin "L8") (pinfunction "VDDQ15_L8") (pintype "power_in"))
      (node (ref "U61") (pin "E4") (pinfunction "VDDQ0_E4") (pintype "power_in"))
      (node (ref "U61") (pin "E8") (pinfunction "VDDQ1_E8") (pintype "power_in"))
      (node (ref "U61") (pin "F4") (pinfunction "VDDQ2_F4") (pintype "power_in"))
      (node (ref "U61") (pin "F8") (pinfunction "VDDQ3_F8") (pintype "power_in"))
      (node (ref "U61") (pin "G4") (pinfunction "VDDQ4_G4") (pintype "power_in"))
      (node (ref "U61") (pin "G8") (pinfunction "VDDQ5_G8") (pintype "power_in"))
      (node (ref "U61") (pin "H3") (pinfunction "VDDQ6_H3") (pintype "power_in"))
      (node (ref "U61") (pin "H4") (pinfunction "VDDQ7_H4") (pintype "power_in"))
      (node (ref "U61") (pin "H8") (pinfunction "VDDQ8_H8") (pintype "power_in"))
      (node (ref "U61") (pin "H9") (pinfunction "VDDQ9_H9") (pintype "power_in"))
      (node (ref "U61") (pin "J4") (pinfunction "VDDQ10_J4") (pintype "power_in"))
      (node (ref "U61") (pin "J8") (pinfunction "VDDQ11_J8") (pintype "power_in"))
      (node (ref "U61") (pin "K4") (pinfunction "VDDQ12_K4") (pintype "power_in"))
      (node (ref "U61") (pin "K8") (pinfunction "VDDQ13_K8") (pintype "power_in"))
      (node (ref "U61") (pin "L4") (pinfunction "VDDQ14_L4") (pintype "power_in"))
      (node (ref "U61") (pin "L8") (pinfunction "VDDQ15_L8") (pintype "power_in"))
      (node (ref "U62") (pin "1") (pinfunction "VDDQSNS_1") (pintype "input"))
      (node (ref "U62") (pin "2") (pinfunction "VLDOIN_2") (pintype "input"))
    )
    (net (code "226") (name "1V8") (class "Default")
      (node (ref "C592") (pin "2") (pinfunction "2_2") (pintype "passive"))
      (node (ref "C593") (pin "2") (pinfunction "2_2") (pintype "passive"))
      (node (ref "C594") (pin "2") (pinfunction "2_2") (pintype "passive"))
      (node (ref "C595") (pin "2") (pinfunction "2_2") (pintype "passive"))
      (node (ref "C596") (pin "2") (pinfunction "2_2") (pintype "passive"))
      (node (ref "C597") (pin "2") (pinfunction "2_2") (pintype "passive"))
      (node (ref "C598") (pin "2") (pinfunction "2_2") (pintype "passive"))
      (node (ref "C599") (pin "2") (pinfunction "2_2") (pintype "passive"))
      (node (ref "C600") (pin "2") (pinfunction "2_2") (pintype "passive"))
      (node (ref "C602") (pin "2") (pinfunction "2_2") (pintype "passive"))
      (node (ref "C603") (pin "2") (pinfunction "2_2") (pintype "passive"))
      (node (ref "C604") (pin "2") (pinfunction "2_2") (pintype "passive"))
      (node (ref "C605") (pin "2") (pinfunction "2_2") (pintype "passive"))
      (node (ref "C606") (pin "2") (pinfunction "2_2") (pintype "passive"))
      (node (ref "C607") (pin "2") (pinfunction "2_2") (pintype "passive"))
      (node (ref "C608") (pin "2") (pinfunction "2_2") (pintype "passive"))
      (node (ref "C609") (pin "2") (pinfunction "2_2") (pintype "passive"))
      (node (ref "C610") (pin "2") (pinfunction "2_2") (pintype "passive"))
      (node (ref "U60") (pin "F5") (pinfunction "VDD0_F5") (pintype "power_in"))
      (node (ref "U60") (pin "F7") (pinfunction "VDD1_F7") (pintype "power_in"))
      (node (ref "U60") (pin "G5") (pinfunction "VDD2_G5") (pintype "power_in"))
      (node (ref "U60") (pin "G7") (pinfunction "VDD3_G7") (pintype "power_in"))
      (node (ref "U60") (pin "H5") (pinfunction "VDD4_H5") (pintype "power_in"))
      (node (ref "U60") (pin "H7") (pinfunction "VDD5_H7") (pintype "power_in"))
      (node (ref "U60") (pin "J5") (pinfunction "VDD6_J5") (pintype "power_in"))
      (node (ref "U60") (pin "J7") (pinfunction "VDD7_J7") (pintype "power_in"))
      (node (ref "U60") (pin "K5") (pinfunction "VDD8_K5") (pintype "power_in"))
      (node (ref "U60") (pin "K7") (pinfunction "VDD9_K7") (pintype "power_in"))
      (node (ref "U61") (pin "F5") (pinfunction "VDD0_F5") (pintype "power_in"))
      (node (ref "U61") (pin "F7") (pinfunction "VDD1_F7") (pintype "power_in"))
      (node (ref "U61") (pin "G5") (pinfunction "VDD2_G5") (pintype "power_in"))
      (node (ref "U61") (pin "G7") (pinfunction "VDD3_G7") (pintype "power_in"))
      (node (ref "U61") (pin "H5") (pinfunction "VDD4_H5") (pintype "power_in"))
      (node (ref "U61") (pin "H7") (pinfunction "VDD5_H7") (pintype "power_in"))
      (node (ref "U61") (pin "J5") (pinfunction "VDD6_J5") (pintype "power_in"))
      (node (ref "U61") (pin "J7") (pinfunction "VDD7_J7") (pintype "power_in"))
      (node (ref "U61") (pin "K5") (pinfunction "VDD8_K5") (pintype "power_in"))
      (node (ref "U61") (pin "K7") (pinfunction "VDD9_K7") (pintype "power_in"))
    )
    (net (code "227") (name "5V") (class "Default")
      (node (ref "C626") (pin "2") (pinfunction "2_2") (pintype "passive"))
      (node (ref "R374") (pin "1") (pinfunction "1_1") (pintype "passive"))
      (node (ref "R375") (pin "1") (pinfunction "1_1") (pintype "passive"))
      (node (ref "U62") (pin "10") (pinfunction "VIN_10") (pintype "input"))
    )
    (net (code "228") (name "GND") (class "Default")
      (node (ref "C572") (pin "1") (pinfunction "1_1") (pintype "passive"))
      (node (ref "C573") (pin "1") (pinfunction "1_1") (pintype "passive"))
      (node (ref "C574") (pin "1") (pinfunction "1_1") (pintype "passive"))
      (node (ref "C575") (pin "1") (pinfunction "1_1") (pintype "passive"))
      (node (ref "C576") (pin "1") (pinfunction "1_1") (pintype "passive"))
      (node (ref "C577") (pin "1") (pinfunction "1_1") (pintype "passive"))
      (node (ref "C578") (pin "1") (pinfunction "1_1") (pintype "passive"))
      (node (ref "C579") (pin "1") (pinfunction "1_1") (pintype "passive"))
      (node (ref "C580") (pin "1") (pinfunction "1_1") (pintype "passive"))
      (node (ref "C582") (pin "1") (pinfunction "1_1") (pintype "passive"))
      (node (ref "C583") (pin "1") (pinfunction "1_1") (pintype "passive"))
      (node (ref "C584") (pin "1") (pinfunction "1_1") (pintype "passive"))
      (node (ref "C585") (pin "1") (pinfunction "1_1") (pintype "passive"))
      (node (ref "C586") (pin "1") (pinfunction "1_1") (pintype "passive"))
      (node (ref "C587") (pin "1") (pinfunction "1_1") (pintype "passive"))
      (node (ref "C588") (pin "1") (pinfunction "1_1") (pintype "passive"))
      (node (ref "C589") (pin "1") (pinfunction "1_1") (pintype "passive"))
      (node (ref "C590") (pin "1") (pinfunction "1_1") (pintype "passive"))
      (node (ref "C592") (pin "1") (pinfunction "1_1") (pintype "passive"))
      (node (ref "C593") (pin "1") (pinfunction "1_1") (pintype "passive"))
      (node (ref "C594") (pin "1") (pinfunction "1_1") (pintype "passive"))
      (node (ref "C595") (pin "1") (pinfunction "1_1") (pintype "passive"))
      (node (ref "C596") (pin "1") (pinfunction "1_1") (pintype "passive"))
      (node (ref "C597") (pin "1") (pinfunction "1_1") (pintype "passive"))
      (node (ref "C598") (pin "1") (pinfunction "1_1") (pintype "passive"))
      (node (ref "C599") (pin "1") (pinfunction "1_1") (pintype "passive"))
      (node (ref "C600") (pin "1") (pinfunction "1_1") (pintype "passive"))
      (node (ref "C602") (pin "1") (pinfunction "1_1") (pintype "passive"))
      (node (ref "C603") (pin "1") (pinfunction "1_1") (pintype "passive"))
      (node (ref "C604") (pin "1") (pinfunction "1_1") (pintype "passive"))
      (node (ref "C605") (pin "1") (pinfunction "1_1") (pintype "passive"))
      (node (ref "C606") (pin "1") (pinfunction "1_1") (pintype "passive"))
      (node (ref "C607") (pin "1") (pinfunction "1_1") (pintype "passive"))
      (node (ref "C608") (pin "1") (pinfunction "1_1") (pintype "passive"))
      (node (ref "C609") (pin "1") (pinfunction "1_1") (pintype "passive"))
      (node (ref "C610") (pin "1") (pinfunction "1_1") (pintype "passive"))
      (node (ref "C612") (pin "1") (pinfunction "1_1") (pintype "passive"))
      (node (ref "C613") (pin "1") (pinfunction "1_1") (pintype "passive"))
      (node (ref "C614") (pin "1") (pinfunction "1_1") (pintype "passive"))
      (node (ref "C615") (pin "1") (pinfunction "1_1") (pintype "passive"))
      (node (ref "C616") (pin "1") (pinfunction "1_1") (pintype "passive"))
      (node (ref "C617") (pin "1") (pinfunction "1_1") (pintype "passive"))
      (node (ref "C618") (pin "1") (pinfunction "1_1") (pintype "passive"))
      (node (ref "C619") (pin "1") (pinfunction "1_1") (pintype "passive"))
      (node (ref "C620") (pin "1") (pinfunction "1_1") (pintype "passive"))
      (node (ref "C621") (pin "1") (pinfunction "1_1") (pintype "passive"))
      (node (ref "C622") (pin "1") (pinfunction "1_1") (pintype "passive"))
      (node (ref "C623") (pin "1") (pinfunction "1_1") (pintype "passive"))
      (node (ref "C624") (pin "1") (pinfunction "1_1") (pintype "passive"))
      (node (ref "C625") (pin "1") (pinfunction "1_1") (pintype "passive"))
      (node (ref "C626") (pin "1") (pinfunction "1_1") (pintype "passive"))
      (node (ref "C627") (pin "1") (pinfunction "1_1") (pintype "passive"))
      (node (ref "C628") (pin "1") (pinfunction "1_1") (pintype "passive"))
      (node (ref "C629") (pin "1") (pinfunction "1_1") (pintype "passive"))
      (node (ref "C630") (pin "1") (pinfunction "1_1") (pintype "passive"))
      (node (ref "C631") (pin "1") (pinfunction "1_1") (pintype "passive"))
      (node (ref "R309") (pin "2") (pinfunction "2_2") (pintype "passive"))
      (node (ref "R310") (pin "2") (pinfunction "2_2") (pintype "passive"))
      (node (ref "R311") (pin "2") (pinfunction "2_2") (pintype "passive"))
      (node (ref "R312") (pin "2") (pinfunction "2_2") (pintype "passive"))
      (node (ref "R313") (pin "2") (pinfunction "2_2") (pintype "passive"))
      (node (ref "R314") (pin "2") (pinfunction "2_2") (pintype "passive"))
      (node (ref "R315") (pin "2") (pinfunction "2_2") (pintype "passive"))
      (node (ref "R316") (pin "2") (pinfunction "2_2") (pintype "passive"))
      (node (ref "R371") (pin "2") (pinfunction "2_2") (pintype "passive"))
      (node (ref "R372") (pin "2") (pinfunction "2_2") (pintype "passive"))
      (node (ref "U60") (pin "C4") (pinfunction "VSS0_C4") (pintype "power_in"))
      (node (ref "U60") (pin "C8") (pinfunction "VSS1_C8") (pintype "power_in"))
      (node (ref "U60") (pin "D4") (pinfunction "VSS2_D4") (pintype "power_in"))
      (node (ref "U60") (pin "D5") (pinfunction "VSS3_D5") (pintype "power_in"))
      (node (ref "U60") (pin "D6") (pinfunction "VSS4_D6") (pintype "power_in"))
      (node (ref "U60") (pin "D7") (pinfunction "VSS5_D7") (pintype "power_in"))
      (node (ref "U60") (pin "D8") (pinfunction "VSS6_D8") (pintype "power_in"))
      (node (ref "U60") (pin "E5") (pinfunction "VSS7_E5") (pintype "power_in"))
      (node (ref "U60") (pin "E6") (pinfunction "VSS8_E6") (pintype "power_in"))
      (node (ref "U60") (pin "E7") (pinfunction "VSS9_E7") (pintype "power_in"))
      (node (ref "U60") (pin "F6") (pinfunction "VSS10_F6") (pintype "power_in"))
      (node (ref "U60") (pin "G6") (pinfunction "VSS11_G6") (pintype "power_in"))
      (node (ref "U60") (pin "H6") (pinfunction "VSS12_H6") (pintype "power_in"))
      (node (ref "U60") (pin "J6") (pinfunction "VSS13_J6") (pintype "power_in"))
      (node (ref "U60") (pin "K6") (pinfunction "VSS14_K6") (pintype "power_in"))
      (node (ref "U60") (pin "L5") (pinfunction "VSS15_L5") (pintype "power_in"))
      (node (ref "U60") (pin "L6") (pinfunction "VSS16_L6") (pintype "power_in"))
      (node (ref "U60") (pin "L7") (pinfunction "VSS17_L7") (pintype "power_in"))
      (node (ref "U60") (pin "M4") (pinfunction "VSS18_M4") (pintype "power_in"))
      (node (ref "U60") (pin "M5") (pinfunction "VSS19_M5") (pintype "power_in"))
      (node (ref "U60") (pin "M6") (pinfunction "VSS20_M6") (pintype "power_in"))
      (node (ref "U60") (pin "M7") (pinfunction "VSS21_M7") (pintype "power_in"))
      (node (ref "U60") (pin "M8") (pinfunction "VSS22_M8") (pintype "power_in"))
      (node (ref "U60") (pin "N4") (pinfunction "VSS23_N4") (pintype "power_in"))
      (node (ref "U60") (pin "N8") (pinfunction "VSS24_N8") (pintype "power_in"))
      (node (ref "U60") (pin "R6") (pinfunction "ODT_R6") (pintype "passive"))
      (node (ref "U61") (pin "C4") (pinfunction "VSS0_C4") (pintype "power_in"))
      (node (ref "U61") (pin "C8") (pinfunction "VSS1_C8") (pintype "power_in"))
      (node (ref "U61") (pin "D4") (pinfunction "VSS2_D4") (pintype "power_in"))
      (node (ref "U61") (pin "D5") (pinfunction "VSS3_D5") (pintype "power_in"))
      (node (ref "U61") (pin "D6") (pinfunction "VSS4_D6") (pintype "power_in"))
      (node (ref "U61") (pin "D7") (pinfunction "VSS5_D7") (pintype "power_in"))
      (node (ref "U61") (pin "D8") (pinfunction "VSS6_D8") (pintype "power_in"))
      (node (ref "U61") (pin "E5") (pinfunction "VSS7_E5") (pintype "power_in"))
      (node (ref "U61") (pin "E6") (pinfunction "VSS8_E6") (pintype "power_in"))
      (node (ref "U61") (pin "E7") (pinfunction "VSS9_E7") (pintype "power_in"))
      (node (ref "U61") (pin "F6") (pinfunction "VSS10_F6") (pintype "power_in"))
      (node (ref "U61") (pin "G6") (pinfunction "VSS11_G6") (pintype "power_in"))
      (node (ref "U61") (pin "H6") (pinfunction "VSS12_H6") (pintype "power_in"))
      (node (ref "U61") (pin "J6") (pinfunction "VSS13_J6") (pintype "power_in"))
      (node (ref "U61") (pin "K6") (pinfunction "VSS14_K6") (pintype "power_in"))
      (node (ref "U61") (pin "L5") (pinfunction "VSS15_L5") (pintype "power_in"))
      (node (ref "U61") (pin "L6") (pinfunction "VSS16_L6") (pintype "power_in"))
      (node (ref "U61") (pin "L7") (pinfunction "VSS17_L7") (pintype "power_in"))
      (node (ref "U61") (pin "M4") (pinfunction "VSS18_M4") (pintype "power_in"))
      (node (ref "U61") (pin "M5") (pinfunction "VSS19_M5") (pintype "power_in"))
      (node (ref "U61") (pin "M6") (pinfunction "VSS20_M6") (pintype "power_in"))
      (node (ref "U61") (pin "M7") (pinfunction "VSS21_M7") (pintype "power_in"))
      (node (ref "U61") (pin "M8") (pinfunction "VSS22_M8") (pintype "power_in"))
      (node (ref "U61") (pin "N4") (pinfunction "VSS23_N4") (pintype "power_in"))
      (node (ref "U61") (pin "N8") (pinfunction "VSS24_N8") (pintype "power_in"))
      (node (ref "U61") (pin "R6") (pinfunction "ODT_R6") (pintype "passive"))
      (node (ref "U62") (pin "11") (pinfunction "PPAD_11") (pintype "passive"))
      (node (ref "U62") (pin "4") (pinfunction "PGND_4") (pintype "passive"))
      (node (ref "U62") (pin "8") (pinfunction "GND_8") (pintype "passive"))
    )
    (net (code "229") (name "Net-(U60A-CQ)") (class "Default")
      (node (ref "TP20") (pin "1") (pinfunction "1_1") (pintype "passive"))
      (node (ref "U60") (pin "A11") (pinfunction "CQ_A11") (pintype "output"))
    )
    (net (code "230") (name "Net-(U60A-QVLD)") (class "Default")
      (node (ref "TP18") (pin "1") (pinfunction "1_1") (pintype "passive"))
      (node (ref "U60") (pin "P6") (pinfunction "QVLD_P6") (pintype "output"))
    )
    (net (code "231") (name "Net-(U60A-ZQ)") (class "Default")
      (node (ref "R371") (pin "1") (pinfunction "1_1") (pintype "passive"))
      (node (ref "U60") (pin "H11") (pinfunction "ZQ_H11") (pintype "passive"))
    )
    (net (code "232") (name "Net-(U61A-CQ)") (class "Default")
      (node (ref "TP21") (pin "1") (pinfunction "1_1") (pintype "passive"))
      (node (ref "U61") (pin "A11") (pinfunction "CQ_A11") (pintype "output"))
    )
    (net (code "233") (name "Net-(U61A-QVLD)") (class "Default")
      (node (ref "TP19") (pin "1") (pinfunction "1_1") (pintype "passive"))
      (node (ref "U61") (pin "P6") (pinfunction "QVLD_P6") (pintype "output"))
    )
    (net (code "234") (name "Net-(U61A-ZQ)") (class "Default")
      (node (ref "R372") (pin "1") (pinfunction "1_1") (pintype "passive"))
      (node (ref "U61") (pin "H11") (pinfunction "ZQ_H11") (pintype "passive"))
    )
    (net (code "235") (name "Net-(U62-S3)") (class "Default")
      (node (ref "R374") (pin "2") (pinfunction "2_2") (pintype "passive"))
      (node (ref "U62") (pin "7") (pinfunction "S3_7") (pintype "input"))
    )
    (net (code "236") (name "Net-(U62-S5)") (class "Default")
      (node (ref "R375") (pin "2") (pinfunction "2_2") (pintype "passive"))
      (node (ref "U62") (pin "9") (pinfunction "S5_9") (pintype "input"))
    )
    (net (code "237") (name "Net-(U62-VTTSNS)") (class "Default")
      (node (ref "C628") (pin "2") (pinfunction "2_2") (pintype "passive"))
      (node (ref "R373") (pin "2") (pinfunction "2_2") (pintype "passive"))
      (node (ref "U62") (pin "5") (pinfunction "VTTSNS_5") (pintype "input"))
    )
    (net (code "238") (name "QDR23_VREF") (class "Default")
      (node (ref "C629") (pin "2") (pinfunction "2_2") (pintype "passive"))
      (node (ref "U60") (pin "H10") (pinfunction "VREF0_H10") (pintype "power_in"))
      (node (ref "U60") (pin "H2") (pinfunction "VREF1_H2") (pintype "power_in"))
      (node (ref "U61") (pin "H10") (pinfunction "VREF0_H10") (pintype "power_in"))
      (node (ref "U61") (pin "H2") (pinfunction "VREF1_H2") (pintype "power_in"))
      (node (ref "U62") (pin "6") (pinfunction "VTTREF_6") (pintype "output"))
    )
    (net (code "239") (name "QDR23_VTT") (class "Default")
      (node (ref "C612") (pin "2") (pinfunction "2_2") (pintype "passive"))
      (node (ref "C613") (pin "2") (pinfunction "2_2") (pintype "passive"))
      (node (ref "C614") (pin "2") (pinfunction "2_2") (pintype "passive"))
      (node (ref "C615") (pin "2") (pinfunction "2_2") (pintype "passive"))
      (node (ref "C616") (pin "2") (pinfunction "2_2") (pintype "passive"))
      (node (ref "C617") (pin "2") (pinfunction "2_2") (pintype "passive"))
      (node (ref "C618") (pin "2") (pinfunction "2_2") (pintype "passive"))
      (node (ref "C619") (pin "2") (pinfunction "2_2") (pintype "passive"))
      (node (ref "C620") (pin "2") (pinfunction "2_2") (pintype "passive"))
      (node (ref "C621") (pin "2") (pinfunction "2_2") (pintype "passive"))
      (node (ref "C622") (pin "2") (pinfunction "2_2") (pintype "passive"))
      (node (ref "C623") (pin "2") (pinfunction "2_2") (pintype "passive"))
      (node (ref "C624") (pin "2") (pinfunction "2_2") (pintype "passive"))
      (node (ref "C625") (pin "2") (pinfunction "2_2") (pintype "passive"))
      (node (ref "C630") (pin "2") (pinfunction "2_2") (pintype "passive"))
      (node (ref "C631") (pin "2") (pinfunction "2_2") (pintype "passive"))
      (node (ref "R278") (pin "2") (pinfunction "2_2") (pintype "passive"))
      (node (ref "R279") (pin "2") (pinfunction "2_2") (pintype "passive"))
      (node (ref "R280") (pin "2") (pinfunction "2_2") (pintype "passive"))
      (node (ref "R281") (pin "2") (pinfunction "2_2") (pintype "passive"))
      (node (ref "R282") (pin "2") (pinfunction "2_2") (pintype "passive"))
      (node (ref "R283") (pin "2") (pinfunction "2_2") (pintype "passive"))
      (node (ref "R373") (pin "1") (pinfunction "1_1") (pintype "passive"))
      (node (ref "RP17") (pin "5") (pinfunction "5_5") (pintype "passive"))
      (node (ref "RP17") (pin "6") (pinfunction "6_6") (pintype "passive"))
      (node (ref "RP17") (pin "7") (pinfunction "7_7") (pintype "passive"))
      (node (ref "RP17") (pin "8") (pinfunction "8_8") (pintype "passive"))
      (node (ref "RP18") (pin "5") (pinfunction "5_5") (pintype "passive"))
      (node (ref "RP18") (pin "6") (pinfunction "6_6") (pintype "passive"))
      (node (ref "RP18") (pin "7") (pinfunction "7_7") (pintype "passive"))
      (node (ref "RP18") (pin "8") (pinfunction "8_8") (pintype "passive"))
      (node (ref "RP19") (pin "5") (pinfunction "5_5") (pintype "passive"))
      (node (ref "RP19") (pin "6") (pinfunction "6_6") (pintype "passive"))
      (node (ref "RP19") (pin "7") (pinfunction "7_7") (pintype "passive"))
      (node (ref "RP19") (pin "8") (pinfunction "8_8") (pintype "passive"))
      (node (ref "RP20") (pin "5") (pinfunction "5_5") (pintype "passive"))
      (node (ref "RP20") (pin "6") (pinfunction "6_6") (pintype "passive"))
      (node (ref "RP20") (pin "7") (pinfunction "7_7") (pintype "passive"))
      (node (ref "RP20") (pin "8") (pinfunction "8_8") (pintype "passive"))
      (node (ref "RP21") (pin "5") (pinfunction "5_5") (pintype "passive"))
      (node (ref "RP21") (pin "6") (pinfunction "6_6") (pintype "passive"))
      (node (ref "RP21") (pin "7") (pinfunction "7_7") (pintype "passive"))
      (node (ref "RP21") (pin "8") (pinfunction "8_8") (pintype "passive"))
      (node (ref "RP22") (pin "5") (pinfunction "5_5") (pintype "passive"))
      (node (ref "RP22") (pin "6") (pinfunction "6_6") (pintype "passive"))
      (node (ref "RP22") (pin "7") (pinfunction "7_7") (pintype "passive"))
      (node (ref "RP22") (pin "8") (pinfunction "8_8") (pintype "passive"))
      (node (ref "RP23") (pin "5") (pinfunction "5_5") (pintype "passive"))
      (node (ref "RP23") (pin "6") (pinfunction "6_6") (pintype "passive"))
      (node (ref "RP23") (pin "7") (pinfunction "7_7") (pintype "passive"))
      (node (ref "RP23") (pin "8") (pinfunction "8_8") (pintype "passive"))
      (node (ref "RP24") (pin "5") (pinfunction "5_5") (pintype "passive"))
      (node (ref "RP24") (pin "6") (pinfunction "6_6") (pintype "passive"))
      (node (ref "RP24") (pin "7") (pinfunction "7_7") (pintype "passive"))
      (node (ref "RP24") (pin "8") (pinfunction "8_8") (pintype "passive"))
      (node (ref "RP25") (pin "5") (pinfunction "5_5") (pintype "passive"))
      (node (ref "RP25") (pin "6") (pinfunction "6_6") (pintype "passive"))
      (node (ref "RP25") (pin "7") (pinfunction "7_7") (pintype "passive"))
      (node (ref "RP25") (pin "8") (pinfunction "8_8") (pintype "passive"))
      (node (ref "RP26") (pin "5") (pinfunction "5_5") (pintype "passive"))
      (node (ref "RP26") (pin "6") (pinfunction "6_6") (pintype "passive"))
      (node (ref "RP26") (pin "7") (pinfunction "7_7") (pintype "passive"))
      (node (ref "RP26") (pin "8") (pinfunction "8_8") (pintype "passive"))
      (node (ref "U62") (pin "3") (pinfunction "VTT_3") (pintype "output"))
    )
    (net (code "240") (name "unconnected-(U60A-CQ#-PadA1)") (class "Default")
      (node (ref "U60") (pin "A1") (pinfunction "CQ#_A1") (pintype "output+no_connect"))
    )
    (net (code "241") (name "unconnected-(U60D-NC1-PadC6)") (class "Default")
      (node (ref "U60") (pin "C6") (pinfunction "NC1_C6") (pintype "passive+no_connect"))
    )
    (net (code "242") (name "unconnected-(U61A-CQ#-PadA1)") (class "Default")
      (node (ref "U61") (pin "A1") (pinfunction "CQ#_A1") (pintype "output+no_connect"))
    )
    (net (code "243") (name "unconnected-(U61D-NC1-PadC6)") (class "Default")
      (node (ref "U61") (pin "C6") (pinfunction "NC1_C6") (pintype "passive+no_connect"))
    )
  )
)
